# MusselGapeTracker_RevE.net
KiCad netlist of a schematic drawn in EAGLE
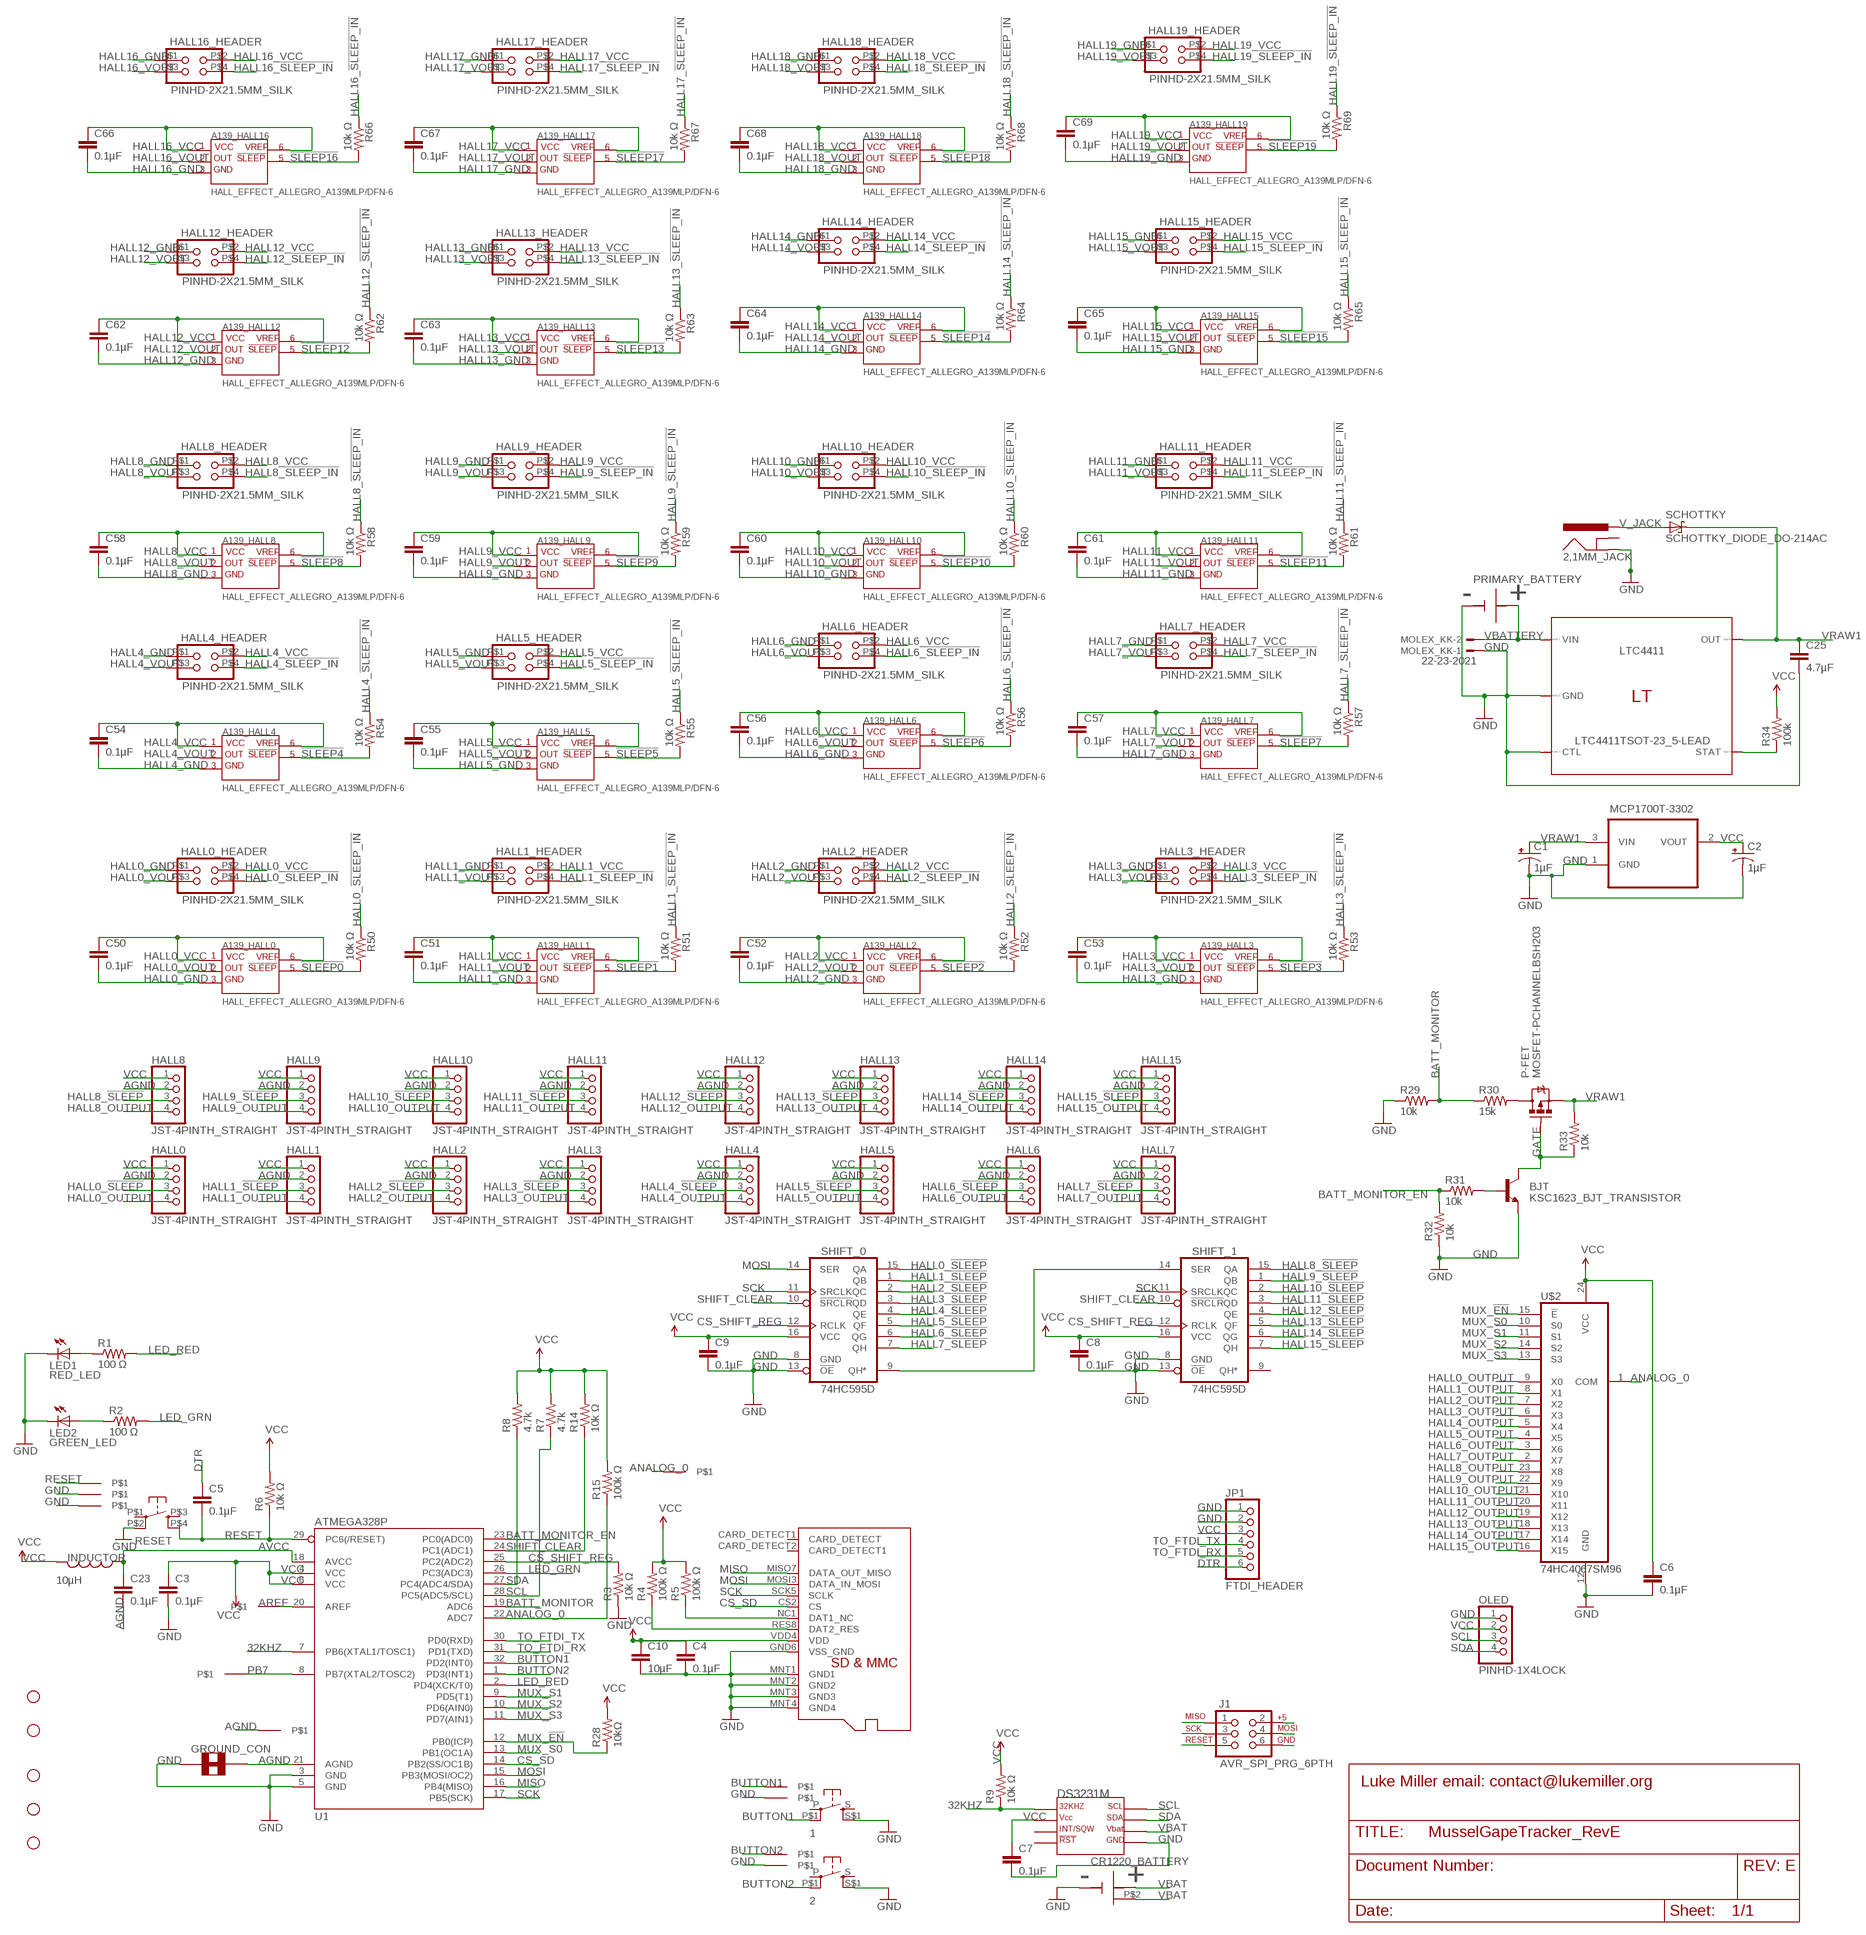
[diagram p0: schematic, sheet 1]

(export (version "E")
  (design (tool "Eeschema 10.0.6"))
  (components
    (comp (ref "1")
      (value "PUSHBUTTON_DPST_SMDSTANDARD")
      (footprint "eagle-import:PUSHBUTTON_DPST_SMD")
      (libsource (lib "eagle-import") (part "PUSHBUTTON_DPST_SMDSTANDARD"))
    )
    (comp (ref "2")
      (value "PUSHBUTTON_DPST_SMDSTANDARD")
      (footprint "eagle-import:PUSHBUTTON_DPST_SMD")
      (libsource (lib "eagle-import") (part "PUSHBUTTON_DPST_SMDSTANDARD"))
    )
    (comp (ref "2,1MM_JACK")
      (value "POWER_JACK_2,1MM")
      (footprint "eagle-import:POWER_JACK_DC_2,1MM")
      (libsource (lib "eagle-import") (part "POWER_JACK_2,1MM"))
    )
    (comp (ref "A139_HALL0")
      (value "HALL_EFFECT_ALLEGRO_A139MLP/DFN-6")
      (footprint "eagle-import:A139__HALL_EFFECT")
      (libsource (lib "eagle-import") (part "HALL_EFFECT_ALLEGRO_A139MLP/DFN-6"))
    )
    (comp (ref "A139_HALL1")
      (value "HALL_EFFECT_ALLEGRO_A139MLP/DFN-6")
      (footprint "eagle-import:A139__HALL_EFFECT")
      (libsource (lib "eagle-import") (part "HALL_EFFECT_ALLEGRO_A139MLP/DFN-6"))
    )
    (comp (ref "A139_HALL2")
      (value "HALL_EFFECT_ALLEGRO_A139MLP/DFN-6")
      (footprint "eagle-import:A139__HALL_EFFECT")
      (libsource (lib "eagle-import") (part "HALL_EFFECT_ALLEGRO_A139MLP/DFN-6"))
    )
    (comp (ref "A139_HALL3")
      (value "HALL_EFFECT_ALLEGRO_A139MLP/DFN-6")
      (footprint "eagle-import:A139__HALL_EFFECT")
      (libsource (lib "eagle-import") (part "HALL_EFFECT_ALLEGRO_A139MLP/DFN-6"))
    )
    (comp (ref "A139_HALL4")
      (value "HALL_EFFECT_ALLEGRO_A139MLP/DFN-6")
      (footprint "eagle-import:A139__HALL_EFFECT")
      (libsource (lib "eagle-import") (part "HALL_EFFECT_ALLEGRO_A139MLP/DFN-6"))
    )
    (comp (ref "A139_HALL5")
      (value "HALL_EFFECT_ALLEGRO_A139MLP/DFN-6")
      (footprint "eagle-import:A139__HALL_EFFECT")
      (libsource (lib "eagle-import") (part "HALL_EFFECT_ALLEGRO_A139MLP/DFN-6"))
    )
    (comp (ref "A139_HALL6")
      (value "HALL_EFFECT_ALLEGRO_A139MLP/DFN-6")
      (footprint "eagle-import:A139__HALL_EFFECT")
      (libsource (lib "eagle-import") (part "HALL_EFFECT_ALLEGRO_A139MLP/DFN-6"))
    )
    (comp (ref "A139_HALL7")
      (value "HALL_EFFECT_ALLEGRO_A139MLP/DFN-6")
      (footprint "eagle-import:A139__HALL_EFFECT")
      (libsource (lib "eagle-import") (part "HALL_EFFECT_ALLEGRO_A139MLP/DFN-6"))
    )
    (comp (ref "A139_HALL8")
      (value "HALL_EFFECT_ALLEGRO_A139MLP/DFN-6")
      (footprint "eagle-import:A139__HALL_EFFECT")
      (libsource (lib "eagle-import") (part "HALL_EFFECT_ALLEGRO_A139MLP/DFN-6"))
    )
    (comp (ref "A139_HALL9")
      (value "HALL_EFFECT_ALLEGRO_A139MLP/DFN-6")
      (footprint "eagle-import:A139__HALL_EFFECT")
      (libsource (lib "eagle-import") (part "HALL_EFFECT_ALLEGRO_A139MLP/DFN-6"))
    )
    (comp (ref "A139_HALL10")
      (value "HALL_EFFECT_ALLEGRO_A139MLP/DFN-6")
      (footprint "eagle-import:A139__HALL_EFFECT")
      (libsource (lib "eagle-import") (part "HALL_EFFECT_ALLEGRO_A139MLP/DFN-6"))
    )
    (comp (ref "A139_HALL11")
      (value "HALL_EFFECT_ALLEGRO_A139MLP/DFN-6")
      (footprint "eagle-import:A139__HALL_EFFECT")
      (libsource (lib "eagle-import") (part "HALL_EFFECT_ALLEGRO_A139MLP/DFN-6"))
    )
    (comp (ref "A139_HALL12")
      (value "HALL_EFFECT_ALLEGRO_A139MLP/DFN-6")
      (footprint "eagle-import:A139__HALL_EFFECT")
      (libsource (lib "eagle-import") (part "HALL_EFFECT_ALLEGRO_A139MLP/DFN-6"))
    )
    (comp (ref "A139_HALL13")
      (value "HALL_EFFECT_ALLEGRO_A139MLP/DFN-6")
      (footprint "eagle-import:A139__HALL_EFFECT")
      (libsource (lib "eagle-import") (part "HALL_EFFECT_ALLEGRO_A139MLP/DFN-6"))
    )
    (comp (ref "A139_HALL14")
      (value "HALL_EFFECT_ALLEGRO_A139MLP/DFN-6")
      (footprint "eagle-import:A139__HALL_EFFECT")
      (libsource (lib "eagle-import") (part "HALL_EFFECT_ALLEGRO_A139MLP/DFN-6"))
    )
    (comp (ref "A139_HALL15")
      (value "HALL_EFFECT_ALLEGRO_A139MLP/DFN-6")
      (footprint "eagle-import:A139__HALL_EFFECT")
      (libsource (lib "eagle-import") (part "HALL_EFFECT_ALLEGRO_A139MLP/DFN-6"))
    )
    (comp (ref "A139_HALL16")
      (value "HALL_EFFECT_ALLEGRO_A139MLP/DFN-6")
      (footprint "eagle-import:A139__HALL_EFFECT")
      (libsource (lib "eagle-import") (part "HALL_EFFECT_ALLEGRO_A139MLP/DFN-6"))
    )
    (comp (ref "A139_HALL17")
      (value "HALL_EFFECT_ALLEGRO_A139MLP/DFN-6")
      (footprint "eagle-import:A139__HALL_EFFECT")
      (libsource (lib "eagle-import") (part "HALL_EFFECT_ALLEGRO_A139MLP/DFN-6"))
    )
    (comp (ref "A139_HALL18")
      (value "HALL_EFFECT_ALLEGRO_A139MLP/DFN-6")
      (footprint "eagle-import:A139__HALL_EFFECT")
      (libsource (lib "eagle-import") (part "HALL_EFFECT_ALLEGRO_A139MLP/DFN-6"))
    )
    (comp (ref "A139_HALL19")
      (value "HALL_EFFECT_ALLEGRO_A139MLP/DFN-6")
      (footprint "eagle-import:A139__HALL_EFFECT")
      (libsource (lib "eagle-import") (part "HALL_EFFECT_ALLEGRO_A139MLP/DFN-6"))
    )
    (comp (ref "BJT")
      (value "KSC1623_BJT_TRANSISTOR")
      (footprint "eagle-import:SOT23")
      (libsource (lib "eagle-import") (part "KSC1623_BJT_TRANSISTOR"))
    )
    (comp (ref "C1")
      (value "1µF")
      (footprint "eagle-import:PANASONIC_B")
      (libsource (lib "eagle-import") (part "CPOL-USB"))
    )
    (comp (ref "C2")
      (value "1µF")
      (footprint "eagle-import:PANASONIC_B")
      (libsource (lib "eagle-import") (part "CPOL-USB"))
    )
    (comp (ref "C3")
      (value "0.1µF")
      (footprint "eagle-import:0603")
      (libsource (lib "eagle-import") (part "CAP0603"))
    )
    (comp (ref "C4")
      (value "0.1µF")
      (footprint "eagle-import:0603")
      (libsource (lib "eagle-import") (part "CAP0603"))
    )
    (comp (ref "C5")
      (value "0.1µF")
      (footprint "eagle-import:0603")
      (libsource (lib "eagle-import") (part "CAP0603"))
    )
    (comp (ref "C6")
      (value "0.1µF")
      (footprint "eagle-import:0603")
      (libsource (lib "eagle-import") (part "CAP0603"))
    )
    (comp (ref "C7")
      (value "0.1µF")
      (footprint "eagle-import:0603")
      (libsource (lib "eagle-import") (part "CAP0603"))
    )
    (comp (ref "C8")
      (value "0.1µF")
      (footprint "eagle-import:0603")
      (libsource (lib "eagle-import") (part "CAP0603"))
    )
    (comp (ref "C9")
      (value "0.1µF")
      (footprint "eagle-import:0603")
      (libsource (lib "eagle-import") (part "CAP0603"))
    )
    (comp (ref "C10")
      (value "10µF")
      (footprint "eagle-import:0603")
      (libsource (lib "eagle-import") (part "CAP0603"))
    )
    (comp (ref "C23")
      (value "0.1µF")
      (footprint "eagle-import:0603")
      (libsource (lib "eagle-import") (part "CAP0603"))
    )
    (comp (ref "C25")
      (value "4.7µF")
      (footprint "eagle-import:0603")
      (libsource (lib "eagle-import") (part "CAP0603"))
    )
    (comp (ref "C50")
      (value "0.1µF")
      (footprint "eagle-import:0603")
      (libsource (lib "eagle-import") (part "CAP0603"))
    )
    (comp (ref "C51")
      (value "0.1µF")
      (footprint "eagle-import:0603")
      (libsource (lib "eagle-import") (part "CAP0603"))
    )
    (comp (ref "C52")
      (value "0.1µF")
      (footprint "eagle-import:0603")
      (libsource (lib "eagle-import") (part "CAP0603"))
    )
    (comp (ref "C53")
      (value "0.1µF")
      (footprint "eagle-import:0603")
      (libsource (lib "eagle-import") (part "CAP0603"))
    )
    (comp (ref "C54")
      (value "0.1µF")
      (footprint "eagle-import:0603")
      (libsource (lib "eagle-import") (part "CAP0603"))
    )
    (comp (ref "C55")
      (value "0.1µF")
      (footprint "eagle-import:0603")
      (libsource (lib "eagle-import") (part "CAP0603"))
    )
    (comp (ref "C56")
      (value "0.1µF")
      (footprint "eagle-import:0603")
      (libsource (lib "eagle-import") (part "CAP0603"))
    )
    (comp (ref "C57")
      (value "0.1µF")
      (footprint "eagle-import:0603")
      (libsource (lib "eagle-import") (part "CAP0603"))
    )
    (comp (ref "C58")
      (value "0.1µF")
      (footprint "eagle-import:0603")
      (libsource (lib "eagle-import") (part "CAP0603"))
    )
    (comp (ref "C59")
      (value "0.1µF")
      (footprint "eagle-import:0603")
      (libsource (lib "eagle-import") (part "CAP0603"))
    )
    (comp (ref "C60")
      (value "0.1µF")
      (footprint "eagle-import:0603")
      (libsource (lib "eagle-import") (part "CAP0603"))
    )
    (comp (ref "C61")
      (value "0.1µF")
      (footprint "eagle-import:0603")
      (libsource (lib "eagle-import") (part "CAP0603"))
    )
    (comp (ref "C62")
      (value "0.1µF")
      (footprint "eagle-import:0603")
      (libsource (lib "eagle-import") (part "CAP0603"))
    )
    (comp (ref "C63")
      (value "0.1µF")
      (footprint "eagle-import:0603")
      (libsource (lib "eagle-import") (part "CAP0603"))
    )
    (comp (ref "C64")
      (value "0.1µF")
      (footprint "eagle-import:0603")
      (libsource (lib "eagle-import") (part "CAP0603"))
    )
    (comp (ref "C65")
      (value "0.1µF")
      (footprint "eagle-import:0603")
      (libsource (lib "eagle-import") (part "CAP0603"))
    )
    (comp (ref "C66")
      (value "0.1µF")
      (footprint "eagle-import:0603")
      (libsource (lib "eagle-import") (part "CAP0603"))
    )
    (comp (ref "C67")
      (value "0.1µF")
      (footprint "eagle-import:0603")
      (libsource (lib "eagle-import") (part "CAP0603"))
    )
    (comp (ref "C68")
      (value "0.1µF")
      (footprint "eagle-import:0603")
      (libsource (lib "eagle-import") (part "CAP0603"))
    )
    (comp (ref "C69")
      (value "0.1µF")
      (footprint "eagle-import:0603")
      (libsource (lib "eagle-import") (part "CAP0603"))
    )
    (comp (ref "CR1220_BATTERY")
      (value "CR1220_BATTERY_HOLDERSMD")
      (footprint "eagle-import:CR1220_BATTERY_HOLDER_SMD")
      (libsource (lib "eagle-import") (part "CR1220_BATTERY_HOLDERSMD"))
    )
    (comp (ref "DS3231M")
      (value "DS3231MSOIC-8")
      (footprint "eagle-import:DS3231M_SOIC8")
      (libsource (lib "eagle-import") (part "DS3231MSOIC-8"))
    )
    (comp (ref "GND")
      (value "PINHD-1X1SMALL")
      (footprint "eagle-import:1X01_SMALL")
      (libsource (lib "eagle-import") (part "PINHD-1X1SMALL"))
    )
    (comp (ref "GROUND_CON")
      (value "SOLDER_JUMPER_TRACESTANDARD")
      (footprint "eagle-import:SJ_2S-TRACE")
      (libsource (lib "eagle-import") (part "SOLDER_JUMPER_TRACESTANDARD"))
    )
    (comp (ref "HALL0")
      (value "JST-4PINTH_STRAIGHT")
      (footprint "eagle-import:JST-PH-4-THM")
      (libsource (lib "eagle-import") (part "JST-4PINTH_STRAIGHT"))
    )
    (comp (ref "HALL0_HEADER")
      (value "PINHD-2X21.5MM_SILK")
      (footprint "eagle-import:2X2_1.5MM")
      (libsource (lib "eagle-import") (part "PINHD-2X21.5MM_SILK"))
    )
    (comp (ref "HALL1")
      (value "JST-4PINTH_STRAIGHT")
      (footprint "eagle-import:JST-PH-4-THM")
      (libsource (lib "eagle-import") (part "JST-4PINTH_STRAIGHT"))
    )
    (comp (ref "HALL1_HEADER")
      (value "PINHD-2X21.5MM_SILK")
      (footprint "eagle-import:2X2_1.5MM")
      (libsource (lib "eagle-import") (part "PINHD-2X21.5MM_SILK"))
    )
    (comp (ref "HALL2")
      (value "JST-4PINTH_STRAIGHT")
      (footprint "eagle-import:JST-PH-4-THM")
      (libsource (lib "eagle-import") (part "JST-4PINTH_STRAIGHT"))
    )
    (comp (ref "HALL2_HEADER")
      (value "PINHD-2X21.5MM_SILK")
      (footprint "eagle-import:2X2_1.5MM")
      (libsource (lib "eagle-import") (part "PINHD-2X21.5MM_SILK"))
    )
    (comp (ref "HALL3")
      (value "JST-4PINTH_STRAIGHT")
      (footprint "eagle-import:JST-PH-4-THM")
      (libsource (lib "eagle-import") (part "JST-4PINTH_STRAIGHT"))
    )
    (comp (ref "HALL3_HEADER")
      (value "PINHD-2X21.5MM_SILK")
      (footprint "eagle-import:2X2_1.5MM")
      (libsource (lib "eagle-import") (part "PINHD-2X21.5MM_SILK"))
    )
    (comp (ref "HALL4")
      (value "JST-4PINTH_STRAIGHT")
      (footprint "eagle-import:JST-PH-4-THM")
      (libsource (lib "eagle-import") (part "JST-4PINTH_STRAIGHT"))
    )
    (comp (ref "HALL4_HEADER")
      (value "PINHD-2X21.5MM_SILK")
      (footprint "eagle-import:2X2_1.5MM")
      (libsource (lib "eagle-import") (part "PINHD-2X21.5MM_SILK"))
    )
    (comp (ref "HALL5")
      (value "JST-4PINTH_STRAIGHT")
      (footprint "eagle-import:JST-PH-4-THM")
      (libsource (lib "eagle-import") (part "JST-4PINTH_STRAIGHT"))
    )
    (comp (ref "HALL5_HEADER")
      (value "PINHD-2X21.5MM_SILK")
      (footprint "eagle-import:2X2_1.5MM")
      (libsource (lib "eagle-import") (part "PINHD-2X21.5MM_SILK"))
    )
    (comp (ref "HALL6")
      (value "JST-4PINTH_STRAIGHT")
      (footprint "eagle-import:JST-PH-4-THM")
      (libsource (lib "eagle-import") (part "JST-4PINTH_STRAIGHT"))
    )
    (comp (ref "HALL6_HEADER")
      (value "PINHD-2X21.5MM_SILK")
      (footprint "eagle-import:2X2_1.5MM")
      (libsource (lib "eagle-import") (part "PINHD-2X21.5MM_SILK"))
    )
    (comp (ref "HALL7")
      (value "JST-4PINTH_STRAIGHT")
      (footprint "eagle-import:JST-PH-4-THM")
      (libsource (lib "eagle-import") (part "JST-4PINTH_STRAIGHT"))
    )
    (comp (ref "HALL7_HEADER")
      (value "PINHD-2X21.5MM_SILK")
      (footprint "eagle-import:2X2_1.5MM")
      (libsource (lib "eagle-import") (part "PINHD-2X21.5MM_SILK"))
    )
    (comp (ref "HALL8")
      (value "JST-4PINTH_STRAIGHT")
      (footprint "eagle-import:JST-PH-4-THM")
      (libsource (lib "eagle-import") (part "JST-4PINTH_STRAIGHT"))
    )
    (comp (ref "HALL8_HEADER")
      (value "PINHD-2X21.5MM_SILK")
      (footprint "eagle-import:2X2_1.5MM")
      (libsource (lib "eagle-import") (part "PINHD-2X21.5MM_SILK"))
    )
    (comp (ref "HALL9")
      (value "JST-4PINTH_STRAIGHT")
      (footprint "eagle-import:JST-PH-4-THM")
      (libsource (lib "eagle-import") (part "JST-4PINTH_STRAIGHT"))
    )
    (comp (ref "HALL9_HEADER")
      (value "PINHD-2X21.5MM_SILK")
      (footprint "eagle-import:2X2_1.5MM")
      (libsource (lib "eagle-import") (part "PINHD-2X21.5MM_SILK"))
    )
    (comp (ref "HALL10")
      (value "JST-4PINTH_STRAIGHT")
      (footprint "eagle-import:JST-PH-4-THM")
      (libsource (lib "eagle-import") (part "JST-4PINTH_STRAIGHT"))
    )
    (comp (ref "HALL10_HEADER")
      (value "PINHD-2X21.5MM_SILK")
      (footprint "eagle-import:2X2_1.5MM")
      (libsource (lib "eagle-import") (part "PINHD-2X21.5MM_SILK"))
    )
    (comp (ref "HALL11")
      (value "JST-4PINTH_STRAIGHT")
      (footprint "eagle-import:JST-PH-4-THM")
      (libsource (lib "eagle-import") (part "JST-4PINTH_STRAIGHT"))
    )
    (comp (ref "HALL11_HEADER")
      (value "PINHD-2X21.5MM_SILK")
      (footprint "eagle-import:2X2_1.5MM")
      (libsource (lib "eagle-import") (part "PINHD-2X21.5MM_SILK"))
    )
    (comp (ref "HALL12")
      (value "JST-4PINTH_STRAIGHT")
      (footprint "eagle-import:JST-PH-4-THM")
      (libsource (lib "eagle-import") (part "JST-4PINTH_STRAIGHT"))
    )
    (comp (ref "HALL12_HEADER")
      (value "PINHD-2X21.5MM_SILK")
      (footprint "eagle-import:2X2_1.5MM")
      (libsource (lib "eagle-import") (part "PINHD-2X21.5MM_SILK"))
    )
    (comp (ref "HALL13")
      (value "JST-4PINTH_STRAIGHT")
      (footprint "eagle-import:JST-PH-4-THM")
      (libsource (lib "eagle-import") (part "JST-4PINTH_STRAIGHT"))
    )
    (comp (ref "HALL13_HEADER")
      (value "PINHD-2X21.5MM_SILK")
      (footprint "eagle-import:2X2_1.5MM")
      (libsource (lib "eagle-import") (part "PINHD-2X21.5MM_SILK"))
    )
    (comp (ref "HALL14")
      (value "JST-4PINTH_STRAIGHT")
      (footprint "eagle-import:JST-PH-4-THM")
      (libsource (lib "eagle-import") (part "JST-4PINTH_STRAIGHT"))
    )
    (comp (ref "HALL14_HEADER")
      (value "PINHD-2X21.5MM_SILK")
      (footprint "eagle-import:2X2_1.5MM")
      (libsource (lib "eagle-import") (part "PINHD-2X21.5MM_SILK"))
    )
    (comp (ref "HALL15")
      (value "JST-4PINTH_STRAIGHT")
      (footprint "eagle-import:JST-PH-4-THM")
      (libsource (lib "eagle-import") (part "JST-4PINTH_STRAIGHT"))
    )
    (comp (ref "HALL15_HEADER")
      (value "PINHD-2X21.5MM_SILK")
      (footprint "eagle-import:2X2_1.5MM")
      (libsource (lib "eagle-import") (part "PINHD-2X21.5MM_SILK"))
    )
    (comp (ref "HALL16_HEADER")
      (value "PINHD-2X21.5MM_SILK")
      (footprint "eagle-import:2X2_1.5MM")
      (libsource (lib "eagle-import") (part "PINHD-2X21.5MM_SILK"))
    )
    (comp (ref "HALL17_HEADER")
      (value "PINHD-2X21.5MM_SILK")
      (footprint "eagle-import:2X2_1.5MM")
      (libsource (lib "eagle-import") (part "PINHD-2X21.5MM_SILK"))
    )
    (comp (ref "HALL18_HEADER")
      (value "PINHD-2X21.5MM_SILK")
      (footprint "eagle-import:2X2_1.5MM")
      (libsource (lib "eagle-import") (part "PINHD-2X21.5MM_SILK"))
    )
    (comp (ref "HALL19_HEADER")
      (value "PINHD-2X21.5MM_SILK")
      (footprint "eagle-import:2X2_1.5MM")
      (libsource (lib "eagle-import") (part "PINHD-2X21.5MM_SILK"))
    )
    (comp (ref "INDUCTOR")
      (value "10µH")
      (footprint "eagle-import:I_0805")
      (libsource (lib "eagle-import") (part "INDUCTOR0805_TY"))
    )
    (comp (ref "J1")
      (value "AVR_SPI_PRG_6PTH")
      (footprint "eagle-import:2X3")
      (libsource (lib "eagle-import") (part "AVR_SPI_PRG_6PTH"))
    )
    (comp (ref "JP1")
      (value "FTDI_HEADER")
      (footprint "eagle-import:1X06-RIGHT_ANGLE")
      (libsource (lib "eagle-import") (part "PINHD-1X6RA"))
    )
    (comp (ref "LED1")
      (value "RED_LED")
      (footprint "eagle-import:CHIPLED_0805")
      (libsource (lib "eagle-import") (part "LED0805"))
    )
    (comp (ref "LED2")
      (value "GREEN_LED")
      (footprint "eagle-import:CHIPLED_0805")
      (libsource (lib "eagle-import") (part "LED0805"))
    )
    (comp (ref "LTC4411")
      (value "LTC4411TSOT-23_5-LEAD")
      (footprint "eagle-import:TSOT-23_5-LEAD")
      (libsource (lib "eagle-import") (part "LTC4411TSOT-23_5-LEAD"))
    )
    (comp (ref "MCP1700T-3302")
      (value "MCP1700T-3302E/TT")
      (footprint "eagle-import:SOT95P237X112-3N")
      (libsource (lib "eagle-import") (part "MCP1700T-3302E/TT"))
    )
    (comp (ref "MOLEX_KK")
      (value "22-23-2021")
      (footprint "eagle-import:22-23-2021")
      (fields (field (name "MF") "MOLEX"))
      (libsource (lib "eagle-import") (part "22-23-2021"))
    )
    (comp (ref "OLED")
      (value "PINHD-1X4LOCK")
      (footprint "eagle-import:1X04_LOCK")
      (libsource (lib "eagle-import") (part "PINHD-1X4LOCK"))
    )
    (comp (ref "P-FET")
      (value "MOSFET-PCHANNELBSH203")
      (footprint "eagle-import:SOT23-3")
      (libsource (lib "eagle-import") (part "MOSFET-PCHANNELBSH203"))
    )
    (comp (ref "PB7")
      (value "PINHD-1X1SMALL")
      (footprint "eagle-import:1X01_SMALL")
      (libsource (lib "eagle-import") (part "PINHD-1X1SMALL"))
    )
    (comp (ref "PRIMARY_BATTERY")
      (value "BATTERY_4XAA")
      (footprint "eagle-import:BATTERY_4XAA_PTH")
      (libsource (lib "eagle-import") (part "BATTERY_4XAA"))
    )
    (comp (ref "R1")
      (value "100 Ω")
      (footprint "eagle-import:R0603")
      (libsource (lib "eagle-import") (part "RESISTOR_SMDR0603"))
    )
    (comp (ref "R2")
      (value "100 Ω")
      (footprint "eagle-import:R0603")
      (libsource (lib "eagle-import") (part "RESISTOR_SMDR0603"))
    )
    (comp (ref "R3")
      (value "10k Ω")
      (footprint "eagle-import:R0603")
      (libsource (lib "eagle-import") (part "RESISTOR_SMDR0603"))
    )
    (comp (ref "R4")
      (value "100k Ω")
      (footprint "eagle-import:R0603")
      (libsource (lib "eagle-import") (part "RESISTOR_SMDR0603"))
    )
    (comp (ref "R5")
      (value "100k Ω")
      (footprint "eagle-import:R0603")
      (libsource (lib "eagle-import") (part "RESISTOR_SMDR0603"))
    )
    (comp (ref "R6")
      (value "10k Ω")
      (footprint "eagle-import:R0603")
      (libsource (lib "eagle-import") (part "RESISTOR_SMDR0603"))
    )
    (comp (ref "R7")
      (value "4.7k")
      (footprint "eagle-import:R0603")
      (libsource (lib "eagle-import") (part "RESISTOR_SMDR0603"))
    )
    (comp (ref "R8")
      (value "4.7k")
      (footprint "eagle-import:R0603")
      (libsource (lib "eagle-import") (part "RESISTOR_SMDR0603"))
    )
    (comp (ref "R9")
      (value "10k Ω")
      (footprint "eagle-import:R0603")
      (libsource (lib "eagle-import") (part "RESISTOR_SMDR0603"))
    )
    (comp (ref "R14")
      (value "10k Ω")
      (footprint "eagle-import:R0603")
      (libsource (lib "eagle-import") (part "RESISTOR_SMDR0603"))
    )
    (comp (ref "R15")
      (value "100k Ω")
      (footprint "eagle-import:R0603")
      (libsource (lib "eagle-import") (part "RESISTOR_SMDR0603"))
    )
    (comp (ref "R28")
      (value "10kΩ")
      (footprint "eagle-import:R0603")
      (libsource (lib "eagle-import") (part "RESISTOR_SMDR0603"))
    )
    (comp (ref "R29")
      (value "10k")
      (footprint "eagle-import:R0603")
      (libsource (lib "eagle-import") (part "RESISTOR_SMDR0603"))
    )
    (comp (ref "R30")
      (value "15k")
      (footprint "eagle-import:R0603")
      (libsource (lib "eagle-import") (part "RESISTOR_SMDR0603"))
    )
    (comp (ref "R31")
      (value "10k")
      (footprint "eagle-import:R0603")
      (libsource (lib "eagle-import") (part "RESISTOR_SMDR0603"))
    )
    (comp (ref "R32")
      (value "10k")
      (footprint "eagle-import:R0603")
      (libsource (lib "eagle-import") (part "RESISTOR_SMDR0603"))
    )
    (comp (ref "R33")
      (value "10k")
      (footprint "eagle-import:R0603")
      (libsource (lib "eagle-import") (part "RESISTOR_SMDR0603"))
    )
    (comp (ref "R34")
      (value "100k")
      (footprint "eagle-import:R0603")
      (libsource (lib "eagle-import") (part "RESISTOR_SMDR0603"))
    )
    (comp (ref "R50")
      (value "10k Ω")
      (footprint "eagle-import:R0603")
      (libsource (lib "eagle-import") (part "RESISTOR_SMDR0603"))
    )
    (comp (ref "R51")
      (value "10k Ω")
      (footprint "eagle-import:R0603")
      (libsource (lib "eagle-import") (part "RESISTOR_SMDR0603"))
    )
    (comp (ref "R52")
      (value "10k Ω")
      (footprint "eagle-import:R0603")
      (libsource (lib "eagle-import") (part "RESISTOR_SMDR0603"))
    )
    (comp (ref "R53")
      (value "10k Ω")
      (footprint "eagle-import:R0603")
      (libsource (lib "eagle-import") (part "RESISTOR_SMDR0603"))
    )
    (comp (ref "R54")
      (value "10k Ω")
      (footprint "eagle-import:R0603")
      (libsource (lib "eagle-import") (part "RESISTOR_SMDR0603"))
    )
    (comp (ref "R55")
      (value "10k Ω")
      (footprint "eagle-import:R0603")
      (libsource (lib "eagle-import") (part "RESISTOR_SMDR0603"))
    )
    (comp (ref "R56")
      (value "10k Ω")
      (footprint "eagle-import:R0603")
      (libsource (lib "eagle-import") (part "RESISTOR_SMDR0603"))
    )
    (comp (ref "R57")
      (value "10k Ω")
      (footprint "eagle-import:R0603")
      (libsource (lib "eagle-import") (part "RESISTOR_SMDR0603"))
    )
    (comp (ref "R58")
      (value "10k Ω")
      (footprint "eagle-import:R0603")
      (libsource (lib "eagle-import") (part "RESISTOR_SMDR0603"))
    )
    (comp (ref "R59")
      (value "10k Ω")
      (footprint "eagle-import:R0603")
      (libsource (lib "eagle-import") (part "RESISTOR_SMDR0603"))
    )
    (comp (ref "R60")
      (value "10k Ω")
      (footprint "eagle-import:R0603")
      (libsource (lib "eagle-import") (part "RESISTOR_SMDR0603"))
    )
    (comp (ref "R61")
      (value "10k Ω")
      (footprint "eagle-import:R0603")
      (libsource (lib "eagle-import") (part "RESISTOR_SMDR0603"))
    )
    (comp (ref "R62")
      (value "10k Ω")
      (footprint "eagle-import:R0603")
      (libsource (lib "eagle-import") (part "RESISTOR_SMDR0603"))
    )
    (comp (ref "R63")
      (value "10k Ω")
      (footprint "eagle-import:R0603")
      (libsource (lib "eagle-import") (part "RESISTOR_SMDR0603"))
    )
    (comp (ref "R64")
      (value "10k Ω")
      (footprint "eagle-import:R0603")
      (libsource (lib "eagle-import") (part "RESISTOR_SMDR0603"))
    )
    (comp (ref "R65")
      (value "10k Ω")
      (footprint "eagle-import:R0603")
      (libsource (lib "eagle-import") (part "RESISTOR_SMDR0603"))
    )
    (comp (ref "R66")
      (value "10k Ω")
      (footprint "eagle-import:R0603")
      (libsource (lib "eagle-import") (part "RESISTOR_SMDR0603"))
    )
    (comp (ref "R67")
      (value "10k Ω")
      (footprint "eagle-import:R0603")
      (libsource (lib "eagle-import") (part "RESISTOR_SMDR0603"))
    )
    (comp (ref "R68")
      (value "10k Ω")
      (footprint "eagle-import:R0603")
      (libsource (lib "eagle-import") (part "RESISTOR_SMDR0603"))
    )
    (comp (ref "R69")
      (value "10k Ω")
      (footprint "eagle-import:R0603")
      (libsource (lib "eagle-import") (part "RESISTOR_SMDR0603"))
    )
    (comp (ref "RESET")
      (value "PUSHBUTTON_DPST_SMDSMALL")
      (footprint "eagle-import:PUSHBUTTON_SPST_PTS525_SERIES")
      (libsource (lib "eagle-import") (part "PUSHBUTTON_DPST_SMDSMALL"))
    )
    (comp (ref "SCHOTTKY")
      (value "SCHOTTKY_DIODE_DO-214AC")
      (footprint "eagle-import:DO214AC")
      (libsource (lib "eagle-import") (part "SCHOTTKY_DIODE_DO-214AC"))
    )
    (comp (ref "SHIFT_0")
      (value "74HC595D")
      (footprint "eagle-import:SO16")
      (libsource (lib "eagle-import") (part "74HC595D"))
    )
    (comp (ref "SHIFT_1")
      (value "74HC595D")
      (footprint "eagle-import:SO16")
      (libsource (lib "eagle-import") (part "74HC595D"))
    )
    (comp (ref "STANDOFF1")
      (value "STAND-OFF4-40")
      (footprint "eagle-import:STAND-OFF")
      (libsource (lib "eagle-import") (part "STAND-OFF4-40"))
    )
    (comp (ref "STANDOFF2")
      (value "STAND-OFF4-40")
      (footprint "eagle-import:STAND-OFF")
      (libsource (lib "eagle-import") (part "STAND-OFF4-40"))
    )
    (comp (ref "STANDOFF3")
      (value "STAND-OFF4-40")
      (footprint "eagle-import:STAND-OFF")
      (libsource (lib "eagle-import") (part "STAND-OFF4-40"))
    )
    (comp (ref "STANDOFF4_M2")
      (value "STAND-OFFM2")
      (footprint "eagle-import:STAND-OFF_M2")
      (libsource (lib "eagle-import") (part "STAND-OFFM2"))
    )
    (comp (ref "STANDOFF5_M2")
      (value "STAND-OFFM2")
      (footprint "eagle-import:STAND-OFF_M2")
      (libsource (lib "eagle-import") (part "STAND-OFFM2"))
    )
    (comp (ref "U$1")
      (value "MICROSD_MOLEX_REVERSECURRENT")
      (footprint "eagle-import:MICROSD_SOCKET_MOLEX_REVERSEMOUNT")
      (libsource (lib "eagle-import") (part "MICROSD_MOLEX_REVERSECURRENT"))
    )
    (comp (ref "U$2")
      (value "74HC4067SM96")
      (footprint "eagle-import:SSOP24")
      (libsource (lib "eagle-import") (part "74HC4067SM96"))
    )
    (comp (ref "U$3")
      (value "PINHD-1X1SMALL")
      (footprint "eagle-import:1X01_SMALL")
      (libsource (lib "eagle-import") (part "PINHD-1X1SMALL"))
    )
    (comp (ref "U$4")
      (value "PINHD-1X1SMALL")
      (footprint "eagle-import:1X01_SMALL")
      (libsource (lib "eagle-import") (part "PINHD-1X1SMALL"))
    )
    (comp (ref "U$6")
      (value "PINHD-1X1SMALL")
      (footprint "eagle-import:1X01_SMALL")
      (libsource (lib "eagle-import") (part "PINHD-1X1SMALL"))
    )
    (comp (ref "U$7")
      (value "PINHD-1X1SMALL")
      (footprint "eagle-import:1X01_SMALL")
      (libsource (lib "eagle-import") (part "PINHD-1X1SMALL"))
    )
    (comp (ref "U$8")
      (value "PINHD-1X1SMALL")
      (footprint "eagle-import:1X01_SMALL")
      (libsource (lib "eagle-import") (part "PINHD-1X1SMALL"))
    )
    (comp (ref "U$9")
      (value "PINHD-1X1SMALL")
      (footprint "eagle-import:1X01_SMALL")
      (libsource (lib "eagle-import") (part "PINHD-1X1SMALL"))
    )
    (comp (ref "U$10")
      (value "PINHD-1X1SMALL")
      (footprint "eagle-import:1X01_SMALL")
      (libsource (lib "eagle-import") (part "PINHD-1X1SMALL"))
    )
    (comp (ref "U$11")
      (value "PINHD-1X1SMALL")
      (footprint "eagle-import:1X01_SMALL")
      (libsource (lib "eagle-import") (part "PINHD-1X1SMALL"))
    )
    (comp (ref "U$17")
      (value "PINHD-1X1SMALL")
      (footprint "eagle-import:1X01_SMALL")
      (libsource (lib "eagle-import") (part "PINHD-1X1SMALL"))
    )
    (comp (ref "U1")
      (value "ATMEGA328P")
      (footprint "eagle-import:TQFP32-08")
      (libsource (lib "eagle-import") (part "ATMEGA328_SMT"))
    )
  )
  (nets
    (net (code "1") (name "/32KHZ") (class "Default")
      (node (ref "DS3231M") (pin "1") (pinfunction "P$1_32KHZ_1") (pintype "bidirectional"))
      (node (ref "R9") (pin "1") (pinfunction "1_1") (pintype "passive"))
      (node (ref "U1") (pin "7") (pinfunction "PB6(XTAL1/TOSC1)_7") (pintype "bidirectional"))
    )
    (net (code "2") (name "/AGND") (class "Default")
      (node (ref "C23") (pin "2") (pinfunction "2_2") (pintype "passive"))
      (node (ref "GROUND_CON") (pin "2") (pinfunction "P$2_2") (pintype "bidirectional"))
      (node (ref "HALL0") (pin "2") (pinfunction "2_2") (pintype "passive"))
      (node (ref "HALL1") (pin "2") (pinfunction "2_2") (pintype "passive"))
      (node (ref "HALL10") (pin "2") (pinfunction "2_2") (pintype "passive"))
      (node (ref "HALL11") (pin "2") (pinfunction "2_2") (pintype "passive"))
      (node (ref "HALL12") (pin "2") (pinfunction "2_2") (pintype "passive"))
      (node (ref "HALL13") (pin "2") (pinfunction "2_2") (pintype "passive"))
      (node (ref "HALL14") (pin "2") (pinfunction "2_2") (pintype "passive"))
      (node (ref "HALL15") (pin "2") (pinfunction "2_2") (pintype "passive"))
      (node (ref "HALL2") (pin "2") (pinfunction "2_2") (pintype "passive"))
      (node (ref "HALL3") (pin "2") (pinfunction "2_2") (pintype "passive"))
      (node (ref "HALL4") (pin "2") (pinfunction "2_2") (pintype "passive"))
      (node (ref "HALL5") (pin "2") (pinfunction "2_2") (pintype "passive"))
      (node (ref "HALL6") (pin "2") (pinfunction "2_2") (pintype "passive"))
      (node (ref "HALL7") (pin "2") (pinfunction "2_2") (pintype "passive"))
      (node (ref "HALL8") (pin "2") (pinfunction "2_2") (pintype "passive"))
      (node (ref "HALL9") (pin "2") (pinfunction "2_2") (pintype "passive"))
      (node (ref "U$11") (pin "1") (pinfunction "P$1_1") (pintype "bidirectional"))
      (node (ref "U1") (pin "21") (pinfunction "AGND_21") (pintype "bidirectional"))
    )
    (net (code "3") (name "/ANALOG_0") (class "Default")
      (node (ref "R15") (pin "1") (pinfunction "1_1") (pintype "passive"))
      (node (ref "U$10") (pin "1") (pinfunction "P$1_1") (pintype "bidirectional"))
      (node (ref "U$2") (pin "1") (pinfunction "COM_1") (pintype "output"))
      (node (ref "U1") (pin "22") (pinfunction "ADC7_22") (pintype "bidirectional"))
    )
    (net (code "4") (name "/AREF") (class "Default")
      (node (ref "U$17") (pin "1") (pinfunction "P$1_1") (pintype "bidirectional"))
      (node (ref "U1") (pin "20") (pinfunction "AREF_20") (pintype "bidirectional"))
    )
    (net (code "5") (name "/AVCC") (class "Default")
      (node (ref "C23") (pin "1") (pinfunction "1_1") (pintype "passive"))
      (node (ref "INDUCTOR") (pin "P$1") (pinfunction "1_P$1") (pintype "passive"))
      (node (ref "U1") (pin "18") (pinfunction "AVCC_18") (pintype "bidirectional"))
    )
    (net (code "6") (name "/BATT_MONITOR") (class "Default")
      (node (ref "R29") (pin "2") (pinfunction "2_2") (pintype "passive"))
      (node (ref "R30") (pin "1") (pinfunction "1_1") (pintype "passive"))
      (node (ref "U1") (pin "19") (pinfunction "ADC6_19") (pintype "bidirectional"))
    )
    (net (code "7") (name "/BATT_MONITOR_EN") (class "Default")
      (node (ref "R31") (pin "1") (pinfunction "1_1") (pintype "passive"))
      (node (ref "R32") (pin "2") (pinfunction "2_2") (pintype "passive"))
      (node (ref "U1") (pin "23") (pinfunction "PC0(ADC0)_23") (pintype "bidirectional"))
    )
    (net (code "8") (name "/BUTTON1") (class "Default")
      (node (ref "1") (pin "P$1") (pinfunction "P1_P$1") (pintype "passive"))
      (node (ref "U$6") (pin "1") (pinfunction "P$1_1") (pintype "bidirectional"))
      (node (ref "U1") (pin "32") (pinfunction "PD2(INT0)_32") (pintype "bidirectional"))
    )
    (net (code "9") (name "/BUTTON2") (class "Default")
      (node (ref "2") (pin "P$1") (pinfunction "P1_P$1") (pintype "passive"))
      (node (ref "U$8") (pin "1") (pinfunction "P$1_1") (pintype "bidirectional"))
      (node (ref "U1") (pin "1") (pinfunction "PD3(INT1)_1") (pintype "bidirectional"))
    )
    (net (code "10") (name "/CS_SD") (class "Default")
      (node (ref "U$1") (pin "CS2") (pinfunction "CS_CS2") (pintype "input"))
      (node (ref "U1") (pin "14") (pinfunction "PB2(SS/OC1B)_14") (pintype "bidirectional"))
    )
    (net (code "11") (name "/CS_SHIFT_REG") (class "Default")
      (node (ref "R3") (pin "2") (pinfunction "2_2") (pintype "passive"))
      (node (ref "SHIFT_0") (pin "12") (pinfunction "RCLK_12") (pintype "input"))
      (node (ref "SHIFT_1") (pin "12") (pinfunction "RCLK_12") (pintype "input"))
      (node (ref "U1") (pin "25") (pinfunction "PC2(ADC2)_25") (pintype "bidirectional"))
    )
    (net (code "12") (name "/DTR") (class "Default")
      (node (ref "C5") (pin "1") (pinfunction "1_1") (pintype "passive"))
      (node (ref "JP1") (pin "6") (pinfunction "6_6") (pintype "passive"))
    )
    (net (code "13") (name "/GATE") (class "Default")
      (node (ref "BJT") (pin "3") (pinfunction "C_3") (pintype "passive"))
      (node (ref "P-FET") (pin "1") (pinfunction "G_1") (pintype "passive"))
      (node (ref "R33") (pin "1") (pinfunction "1_1") (pintype "passive"))
    )
    (net (code "14") (name "/HALL0_GND") (class "Default")
      (node (ref "A139_HALL0") (pin "P$3_4") (pinfunction "P$3_P$3_4") (pintype "bidirectional"))
      (node (ref "C50") (pin "2") (pinfunction "2_2") (pintype "passive"))
      (node (ref "HALL0_HEADER") (pin "P$1") (pinfunction "1_P$1") (pintype "passive"))
    )
    (net (code "15") (name "/HALL0_OUTPUT") (class "Default")
      (node (ref "HALL0") (pin "4") (pinfunction "4_4") (pintype "passive"))
      (node (ref "U$2") (pin "9") (pinfunction "X0_9") (pintype "input"))
    )
    (net (code "16") (name "/HALL0_VCC") (class "Default")
      (node (ref "A139_HALL0") (pin "P$1") (pinfunction "P$1_P$1") (pintype "bidirectional"))
      (node (ref "A139_HALL0") (pin "P$6") (pinfunction "P$6_P$6") (pintype "bidirectional"))
      (node (ref "C50") (pin "1") (pinfunction "1_1") (pintype "passive"))
      (node (ref "HALL0_HEADER") (pin "P$2") (pinfunction "2_P$2") (pintype "passive"))
    )
    (net (code "17") (name "/HALL0_VOUT") (class "Default")
      (node (ref "A139_HALL0") (pin "P$2") (pinfunction "P$2_P$2") (pintype "bidirectional"))
      (node (ref "HALL0_HEADER") (pin "P$3") (pinfunction "3_P$3") (pintype "passive"))
    )
    (net (code "18") (name "/HALL0_~{SLEEP_IN}") (class "Default")
      (node (ref "HALL0_HEADER") (pin "P$4") (pinfunction "4_P$4") (pintype "passive"))
      (node (ref "R50") (pin "1") (pinfunction "1_1") (pintype "passive"))
    )
    (net (code "19") (name "/HALL0_~{SLEEP}") (class "Default")
      (node (ref "HALL0") (pin "3") (pinfunction "3_3") (pintype "passive"))
      (node (ref "SHIFT_0") (pin "15") (pinfunction "QA_15") (pintype "tri_state"))
    )
    (net (code "20") (name "/HALL1_GND") (class "Default")
      (node (ref "A139_HALL1") (pin "P$3_4") (pinfunction "P$3_P$3_4") (pintype "bidirectional"))
      (node (ref "C51") (pin "2") (pinfunction "2_2") (pintype "passive"))
      (node (ref "HALL1_HEADER") (pin "P$1") (pinfunction "1_P$1") (pintype "passive"))
    )
    (net (code "21") (name "/HALL1_OUTPUT") (class "Default")
      (node (ref "HALL1") (pin "4") (pinfunction "4_4") (pintype "passive"))
      (node (ref "U$2") (pin "8") (pinfunction "X1_8") (pintype "input"))
    )
    (net (code "22") (name "/HALL1_VCC") (class "Default")
      (node (ref "A139_HALL1") (pin "P$1") (pinfunction "P$1_P$1") (pintype "bidirectional"))
      (node (ref "A139_HALL1") (pin "P$6") (pinfunction "P$6_P$6") (pintype "bidirectional"))
      (node (ref "C51") (pin "1") (pinfunction "1_1") (pintype "passive"))
      (node (ref "HALL1_HEADER") (pin "P$2") (pinfunction "2_P$2") (pintype "passive"))
    )
    (net (code "23") (name "/HALL1_VOUT") (class "Default")
      (node (ref "A139_HALL1") (pin "P$2") (pinfunction "P$2_P$2") (pintype "bidirectional"))
      (node (ref "HALL1_HEADER") (pin "P$3") (pinfunction "3_P$3") (pintype "passive"))
    )
    (net (code "24") (name "/HALL1_~{SLEEP_IN}") (class "Default")
      (node (ref "HALL1_HEADER") (pin "P$4") (pinfunction "4_P$4") (pintype "passive"))
      (node (ref "R51") (pin "1") (pinfunction "1_1") (pintype "passive"))
    )
    (net (code "25") (name "/HALL1_~{SLEEP}") (class "Default")
      (node (ref "HALL1") (pin "3") (pinfunction "3_3") (pintype "passive"))
      (node (ref "SHIFT_0") (pin "1") (pinfunction "QB_1") (pintype "tri_state"))
    )
    (net (code "26") (name "/HALL2_GND") (class "Default")
      (node (ref "A139_HALL2") (pin "P$3_4") (pinfunction "P$3_P$3_4") (pintype "bidirectional"))
      (node (ref "C52") (pin "2") (pinfunction "2_2") (pintype "passive"))
      (node (ref "HALL2_HEADER") (pin "P$1") (pinfunction "1_P$1") (pintype "passive"))
    )
    (net (code "27") (name "/HALL2_OUTPUT") (class "Default")
      (node (ref "HALL2") (pin "4") (pinfunction "4_4") (pintype "passive"))
      (node (ref "U$2") (pin "7") (pinfunction "X2_7") (pintype "input"))
    )
    (net (code "28") (name "/HALL2_VCC") (class "Default")
      (node (ref "A139_HALL2") (pin "P$1") (pinfunction "P$1_P$1") (pintype "bidirectional"))
      (node (ref "A139_HALL2") (pin "P$6") (pinfunction "P$6_P$6") (pintype "bidirectional"))
      (node (ref "C52") (pin "1") (pinfunction "1_1") (pintype "passive"))
      (node (ref "HALL2_HEADER") (pin "P$2") (pinfunction "2_P$2") (pintype "passive"))
    )
    (net (code "29") (name "/HALL2_VOUT") (class "Default")
      (node (ref "A139_HALL2") (pin "P$2") (pinfunction "P$2_P$2") (pintype "bidirectional"))
      (node (ref "HALL2_HEADER") (pin "P$3") (pinfunction "3_P$3") (pintype "passive"))
    )
    (net (code "30") (name "/HALL2_~{SLEEP_IN}") (class "Default")
      (node (ref "HALL2_HEADER") (pin "P$4") (pinfunction "4_P$4") (pintype "passive"))
      (node (ref "R52") (pin "1") (pinfunction "1_1") (pintype "passive"))
    )
    (net (code "31") (name "/HALL2_~{SLEEP}") (class "Default")
      (node (ref "HALL2") (pin "3") (pinfunction "3_3") (pintype "passive"))
      (node (ref "SHIFT_0") (pin "2") (pinfunction "QC_2") (pintype "tri_state"))
    )
    (net (code "32") (name "/HALL3_GND") (class "Default")
      (node (ref "A139_HALL3") (pin "P$3_4") (pinfunction "P$3_P$3_4") (pintype "bidirectional"))
      (node (ref "C53") (pin "2") (pinfunction "2_2") (pintype "passive"))
      (node (ref "HALL3_HEADER") (pin "P$1") (pinfunction "1_P$1") (pintype "passive"))
    )
    (net (code "33") (name "/HALL3_OUTPUT") (class "Default")
      (node (ref "HALL3") (pin "4") (pinfunction "4_4") (pintype "passive"))
      (node (ref "U$2") (pin "6") (pinfunction "X3_6") (pintype "input"))
    )
    (net (code "34") (name "/HALL3_VCC") (class "Default")
      (node (ref "A139_HALL3") (pin "P$1") (pinfunction "P$1_P$1") (pintype "bidirectional"))
      (node (ref "A139_HALL3") (pin "P$6") (pinfunction "P$6_P$6") (pintype "bidirectional"))
      (node (ref "C53") (pin "1") (pinfunction "1_1") (pintype "passive"))
      (node (ref "HALL3_HEADER") (pin "P$2") (pinfunction "2_P$2") (pintype "passive"))
    )
    (net (code "35") (name "/HALL3_VOUT") (class "Default")
      (node (ref "A139_HALL3") (pin "P$2") (pinfunction "P$2_P$2") (pintype "bidirectional"))
      (node (ref "HALL3_HEADER") (pin "P$3") (pinfunction "3_P$3") (pintype "passive"))
    )
    (net (code "36") (name "/HALL3_~{SLEEP_IN}") (class "Default")
      (node (ref "HALL3_HEADER") (pin "P$4") (pinfunction "4_P$4") (pintype "passive"))
      (node (ref "R53") (pin "1") (pinfunction "1_1") (pintype "passive"))
    )
    (net (code "37") (name "/HALL3_~{SLEEP}") (class "Default")
      (node (ref "HALL3") (pin "3") (pinfunction "3_3") (pintype "passive"))
      (node (ref "SHIFT_0") (pin "3") (pinfunction "QD_3") (pintype "tri_state"))
    )
    (net (code "38") (name "/HALL4_GND") (class "Default")
      (node (ref "A139_HALL4") (pin "P$3_4") (pinfunction "P$3_P$3_4") (pintype "bidirectional"))
      (node (ref "C54") (pin "2") (pinfunction "2_2") (pintype "passive"))
      (node (ref "HALL4_HEADER") (pin "P$1") (pinfunction "1_P$1") (pintype "passive"))
    )
    (net (code "39") (name "/HALL4_OUTPUT") (class "Default")
      (node (ref "HALL4") (pin "4") (pinfunction "4_4") (pintype "passive"))
      (node (ref "U$2") (pin "5") (pinfunction "X4_5") (pintype "input"))
    )
    (net (code "40") (name "/HALL4_VCC") (class "Default")
      (node (ref "A139_HALL4") (pin "P$1") (pinfunction "P$1_P$1") (pintype "bidirectional"))
      (node (ref "A139_HALL4") (pin "P$6") (pinfunction "P$6_P$6") (pintype "bidirectional"))
      (node (ref "C54") (pin "1") (pinfunction "1_1") (pintype "passive"))
      (node (ref "HALL4_HEADER") (pin "P$2") (pinfunction "2_P$2") (pintype "passive"))
    )
    (net (code "41") (name "/HALL4_VOUT") (class "Default")
      (node (ref "A139_HALL4") (pin "P$2") (pinfunction "P$2_P$2") (pintype "bidirectional"))
      (node (ref "HALL4_HEADER") (pin "P$3") (pinfunction "3_P$3") (pintype "passive"))
    )
    (net (code "42") (name "/HALL4_~{SLEEP_IN}") (class "Default")
      (node (ref "HALL4_HEADER") (pin "P$4") (pinfunction "4_P$4") (pintype "passive"))
      (node (ref "R54") (pin "1") (pinfunction "1_1") (pintype "passive"))
    )
    (net (code "43") (name "/HALL4_~{SLEEP}") (class "Default")
      (node (ref "HALL4") (pin "3") (pinfunction "3_3") (pintype "passive"))
      (node (ref "SHIFT_0") (pin "4") (pinfunction "QE_4") (pintype "tri_state"))
    )
    (net (code "44") (name "/HALL5_GND") (class "Default")
      (node (ref "A139_HALL5") (pin "P$3_4") (pinfunction "P$3_P$3_4") (pintype "bidirectional"))
      (node (ref "C55") (pin "2") (pinfunction "2_2") (pintype "passive"))
      (node (ref "HALL5_HEADER") (pin "P$1") (pinfunction "1_P$1") (pintype "passive"))
    )
    (net (code "45") (name "/HALL5_OUTPUT") (class "Default")
      (node (ref "HALL5") (pin "4") (pinfunction "4_4") (pintype "passive"))
      (node (ref "U$2") (pin "4") (pinfunction "X5_4") (pintype "input"))
    )
    (net (code "46") (name "/HALL5_VCC") (class "Default")
      (node (ref "A139_HALL5") (pin "P$1") (pinfunction "P$1_P$1") (pintype "bidirectional"))
      (node (ref "A139_HALL5") (pin "P$6") (pinfunction "P$6_P$6") (pintype "bidirectional"))
      (node (ref "C55") (pin "1") (pinfunction "1_1") (pintype "passive"))
      (node (ref "HALL5_HEADER") (pin "P$2") (pinfunction "2_P$2") (pintype "passive"))
    )
    (net (code "47") (name "/HALL5_VOUT") (class "Default")
      (node (ref "A139_HALL5") (pin "P$2") (pinfunction "P$2_P$2") (pintype "bidirectional"))
      (node (ref "HALL5_HEADER") (pin "P$3") (pinfunction "3_P$3") (pintype "passive"))
    )
    (net (code "48") (name "/HALL5_~{SLEEP_IN}") (class "Default")
      (node (ref "HALL5_HEADER") (pin "P$4") (pinfunction "4_P$4") (pintype "passive"))
      (node (ref "R55") (pin "1") (pinfunction "1_1") (pintype "passive"))
    )
    (net (code "49") (name "/HALL5_~{SLEEP}") (class "Default")
      (node (ref "HALL5") (pin "3") (pinfunction "3_3") (pintype "passive"))
      (node (ref "SHIFT_0") (pin "5") (pinfunction "QF_5") (pintype "tri_state"))
    )
    (net (code "50") (name "/HALL6_GND") (class "Default")
      (node (ref "A139_HALL6") (pin "P$3_4") (pinfunction "P$3_P$3_4") (pintype "bidirectional"))
      (node (ref "C56") (pin "2") (pinfunction "2_2") (pintype "passive"))
      (node (ref "HALL6_HEADER") (pin "P$1") (pinfunction "1_P$1") (pintype "passive"))
    )
    (net (code "51") (name "/HALL6_OUTPUT") (class "Default")
      (node (ref "HALL6") (pin "4") (pinfunction "4_4") (pintype "passive"))
      (node (ref "U$2") (pin "3") (pinfunction "X6_3") (pintype "input"))
    )
    (net (code "52") (name "/HALL6_VCC") (class "Default")
      (node (ref "A139_HALL6") (pin "P$1") (pinfunction "P$1_P$1") (pintype "bidirectional"))
      (node (ref "A139_HALL6") (pin "P$6") (pinfunction "P$6_P$6") (pintype "bidirectional"))
      (node (ref "C56") (pin "1") (pinfunction "1_1") (pintype "passive"))
      (node (ref "HALL6_HEADER") (pin "P$2") (pinfunction "2_P$2") (pintype "passive"))
    )
    (net (code "53") (name "/HALL6_VOUT") (class "Default")
      (node (ref "A139_HALL6") (pin "P$2") (pinfunction "P$2_P$2") (pintype "bidirectional"))
      (node (ref "HALL6_HEADER") (pin "P$3") (pinfunction "3_P$3") (pintype "passive"))
    )
    (net (code "54") (name "/HALL6_~{SLEEP_IN}") (class "Default")
      (node (ref "HALL6_HEADER") (pin "P$4") (pinfunction "4_P$4") (pintype "passive"))
      (node (ref "R56") (pin "1") (pinfunction "1_1") (pintype "passive"))
    )
    (net (code "55") (name "/HALL6_~{SLEEP}") (class "Default")
      (node (ref "HALL6") (pin "3") (pinfunction "3_3") (pintype "passive"))
      (node (ref "SHIFT_0") (pin "6") (pinfunction "QG_6") (pintype "tri_state"))
    )
    (net (code "56") (name "/HALL7_GND") (class "Default")
      (node (ref "A139_HALL7") (pin "P$3_4") (pinfunction "P$3_P$3_4") (pintype "bidirectional"))
      (node (ref "C57") (pin "2") (pinfunction "2_2") (pintype "passive"))
      (node (ref "HALL7_HEADER") (pin "P$1") (pinfunction "1_P$1") (pintype "passive"))
    )
    (net (code "57") (name "/HALL7_OUTPUT") (class "Default")
      (node (ref "HALL7") (pin "4") (pinfunction "4_4") (pintype "passive"))
      (node (ref "U$2") (pin "2") (pinfunction "X7_2") (pintype "input"))
    )
    (net (code "58") (name "/HALL7_VCC") (class "Default")
      (node (ref "A139_HALL7") (pin "P$1") (pinfunction "P$1_P$1") (pintype "bidirectional"))
      (node (ref "A139_HALL7") (pin "P$6") (pinfunction "P$6_P$6") (pintype "bidirectional"))
      (node (ref "C57") (pin "1") (pinfunction "1_1") (pintype "passive"))
      (node (ref "HALL7_HEADER") (pin "P$2") (pinfunction "2_P$2") (pintype "passive"))
    )
    (net (code "59") (name "/HALL7_VOUT") (class "Default")
      (node (ref "A139_HALL7") (pin "P$2") (pinfunction "P$2_P$2") (pintype "bidirectional"))
      (node (ref "HALL7_HEADER") (pin "P$3") (pinfunction "3_P$3") (pintype "passive"))
    )
    (net (code "60") (name "/HALL7_~{SLEEP_IN}") (class "Default")
      (node (ref "HALL7_HEADER") (pin "P$4") (pinfunction "4_P$4") (pintype "passive"))
      (node (ref "R57") (pin "1") (pinfunction "1_1") (pintype "passive"))
    )
    (net (code "61") (name "/HALL7_~{SLEEP}") (class "Default")
      (node (ref "HALL7") (pin "3") (pinfunction "3_3") (pintype "passive"))
      (node (ref "SHIFT_0") (pin "7") (pinfunction "QH_7") (pintype "tri_state"))
    )
    (net (code "62") (name "/HALL8_GND") (class "Default")
      (node (ref "A139_HALL8") (pin "P$3_4") (pinfunction "P$3_P$3_4") (pintype "bidirectional"))
      (node (ref "C58") (pin "2") (pinfunction "2_2") (pintype "passive"))
      (node (ref "HALL8_HEADER") (pin "P$1") (pinfunction "1_P$1") (pintype "passive"))
    )
    (net (code "63") (name "/HALL8_OUTPUT") (class "Default")
      (node (ref "HALL8") (pin "4") (pinfunction "4_4") (pintype "passive"))
      (node (ref "U$2") (pin "23") (pinfunction "X8_23") (pintype "input"))
    )
    (net (code "64") (name "/HALL8_VCC") (class "Default")
      (node (ref "A139_HALL8") (pin "P$1") (pinfunction "P$1_P$1") (pintype "bidirectional"))
      (node (ref "A139_HALL8") (pin "P$6") (pinfunction "P$6_P$6") (pintype "bidirectional"))
      (node (ref "C58") (pin "1") (pinfunction "1_1") (pintype "passive"))
      (node (ref "HALL8_HEADER") (pin "P$2") (pinfunction "2_P$2") (pintype "passive"))
    )
    (net (code "65") (name "/HALL8_VOUT") (class "Default")
      (node (ref "A139_HALL8") (pin "P$2") (pinfunction "P$2_P$2") (pintype "bidirectional"))
      (node (ref "HALL8_HEADER") (pin "P$3") (pinfunction "3_P$3") (pintype "passive"))
    )
    (net (code "66") (name "/HALL8_~{SLEEP_IN}") (class "Default")
      (node (ref "HALL8_HEADER") (pin "P$4") (pinfunction "4_P$4") (pintype "passive"))
      (node (ref "R58") (pin "1") (pinfunction "1_1") (pintype "passive"))
    )
    (net (code "67") (name "/HALL8_~{SLEEP}") (class "Default")
      (node (ref "HALL8") (pin "3") (pinfunction "3_3") (pintype "passive"))
      (node (ref "SHIFT_1") (pin "15") (pinfunction "QA_15") (pintype "tri_state"))
    )
    (net (code "68") (name "/HALL9_GND") (class "Default")
      (node (ref "A139_HALL9") (pin "P$3_4") (pinfunction "P$3_P$3_4") (pintype "bidirectional"))
      (node (ref "C59") (pin "2") (pinfunction "2_2") (pintype "passive"))
      (node (ref "HALL9_HEADER") (pin "P$1") (pinfunction "1_P$1") (pintype "passive"))
    )
    (net (code "69") (name "/HALL9_OUTPUT") (class "Default")
      (node (ref "HALL9") (pin "4") (pinfunction "4_4") (pintype "passive"))
      (node (ref "U$2") (pin "22") (pinfunction "X9_22") (pintype "input"))
    )
    (net (code "70") (name "/HALL9_VCC") (class "Default")
      (node (ref "A139_HALL9") (pin "P$1") (pinfunction "P$1_P$1") (pintype "bidirectional"))
      (node (ref "A139_HALL9") (pin "P$6") (pinfunction "P$6_P$6") (pintype "bidirectional"))
      (node (ref "C59") (pin "1") (pinfunction "1_1") (pintype "passive"))
      (node (ref "HALL9_HEADER") (pin "P$2") (pinfunction "2_P$2") (pintype "passive"))
    )
    (net (code "71") (name "/HALL9_VOUT") (class "Default")
      (node (ref "A139_HALL9") (pin "P$2") (pinfunction "P$2_P$2") (pintype "bidirectional"))
      (node (ref "HALL9_HEADER") (pin "P$3") (pinfunction "3_P$3") (pintype "passive"))
    )
    (net (code "72") (name "/HALL9_~{SLEEP_IN}") (class "Default")
      (node (ref "HALL9_HEADER") (pin "P$4") (pinfunction "4_P$4") (pintype "passive"))
      (node (ref "R59") (pin "1") (pinfunction "1_1") (pintype "passive"))
    )
    (net (code "73") (name "/HALL9_~{SLEEP}") (class "Default")
      (node (ref "HALL9") (pin "3") (pinfunction "3_3") (pintype "passive"))
      (node (ref "SHIFT_1") (pin "1") (pinfunction "QB_1") (pintype "tri_state"))
    )
    (net (code "74") (name "/HALL10_GND") (class "Default")
      (node (ref "A139_HALL10") (pin "P$3_4") (pinfunction "P$3_P$3_4") (pintype "bidirectional"))
      (node (ref "C60") (pin "2") (pinfunction "2_2") (pintype "passive"))
      (node (ref "HALL10_HEADER") (pin "P$1") (pinfunction "1_P$1") (pintype "passive"))
    )
    (net (code "75") (name "/HALL10_OUTPUT") (class "Default")
      (node (ref "HALL10") (pin "4") (pinfunction "4_4") (pintype "passive"))
      (node (ref "U$2") (pin "21") (pinfunction "X10_21") (pintype "input"))
    )
    (net (code "76") (name "/HALL10_VCC") (class "Default")
      (node (ref "A139_HALL10") (pin "P$1") (pinfunction "P$1_P$1") (pintype "bidirectional"))
      (node (ref "A139_HALL10") (pin "P$6") (pinfunction "P$6_P$6") (pintype "bidirectional"))
      (node (ref "C60") (pin "1") (pinfunction "1_1") (pintype "passive"))
      (node (ref "HALL10_HEADER") (pin "P$2") (pinfunction "2_P$2") (pintype "passive"))
    )
    (net (code "77") (name "/HALL10_VOUT") (class "Default")
      (node (ref "A139_HALL10") (pin "P$2") (pinfunction "P$2_P$2") (pintype "bidirectional"))
      (node (ref "HALL10_HEADER") (pin "P$3") (pinfunction "3_P$3") (pintype "passive"))
    )
    (net (code "78") (name "/HALL10_~{SLEEP_IN}") (class "Default")
      (node (ref "HALL10_HEADER") (pin "P$4") (pinfunction "4_P$4") (pintype "passive"))
      (node (ref "R60") (pin "1") (pinfunction "1_1") (pintype "passive"))
    )
    (net (code "79") (name "/HALL10_~{SLEEP}") (class "Default")
      (node (ref "HALL10") (pin "3") (pinfunction "3_3") (pintype "passive"))
      (node (ref "SHIFT_1") (pin "2") (pinfunction "QC_2") (pintype "tri_state"))
    )
    (net (code "80") (name "/HALL11_GND") (class "Default")
      (node (ref "A139_HALL11") (pin "P$3_4") (pinfunction "P$3_P$3_4") (pintype "bidirectional"))
      (node (ref "C61") (pin "2") (pinfunction "2_2") (pintype "passive"))
      (node (ref "HALL11_HEADER") (pin "P$1") (pinfunction "1_P$1") (pintype "passive"))
    )
    (net (code "81") (name "/HALL11_OUTPUT") (class "Default")
      (node (ref "HALL11") (pin "4") (pinfunction "4_4") (pintype "passive"))
      (node (ref "U$2") (pin "20") (pinfunction "X11_20") (pintype "input"))
    )
    (net (code "82") (name "/HALL11_VCC") (class "Default")
      (node (ref "A139_HALL11") (pin "P$1") (pinfunction "P$1_P$1") (pintype "bidirectional"))
      (node (ref "A139_HALL11") (pin "P$6") (pinfunction "P$6_P$6") (pintype "bidirectional"))
      (node (ref "C61") (pin "1") (pinfunction "1_1") (pintype "passive"))
      (node (ref "HALL11_HEADER") (pin "P$2") (pinfunction "2_P$2") (pintype "passive"))
    )
    (net (code "83") (name "/HALL11_VOUT") (class "Default")
      (node (ref "A139_HALL11") (pin "P$2") (pinfunction "P$2_P$2") (pintype "bidirectional"))
      (node (ref "HALL11_HEADER") (pin "P$3") (pinfunction "3_P$3") (pintype "passive"))
    )
    (net (code "84") (name "/HALL11_~{SLEEP_IN}") (class "Default")
      (node (ref "HALL11_HEADER") (pin "P$4") (pinfunction "4_P$4") (pintype "passive"))
      (node (ref "R61") (pin "1") (pinfunction "1_1") (pintype "passive"))
    )
    (net (code "85") (name "/HALL11_~{SLEEP}") (class "Default")
      (node (ref "HALL11") (pin "3") (pinfunction "3_3") (pintype "passive"))
      (node (ref "SHIFT_1") (pin "3") (pinfunction "QD_3") (pintype "tri_state"))
    )
    (net (code "86") (name "/HALL12_GND") (class "Default")
      (node (ref "A139_HALL12") (pin "P$3_4") (pinfunction "P$3_P$3_4") (pintype "bidirectional"))
      (node (ref "C62") (pin "2") (pinfunction "2_2") (pintype "passive"))
      (node (ref "HALL12_HEADER") (pin "P$1") (pinfunction "1_P$1") (pintype "passive"))
    )
    (net (code "87") (name "/HALL12_OUTPUT") (class "Default")
      (node (ref "HALL12") (pin "4") (pinfunction "4_4") (pintype "passive"))
      (node (ref "U$2") (pin "19") (pinfunction "X12_19") (pintype "input"))
    )
    (net (code "88") (name "/HALL12_VCC") (class "Default")
      (node (ref "A139_HALL12") (pin "P$1") (pinfunction "P$1_P$1") (pintype "bidirectional"))
      (node (ref "A139_HALL12") (pin "P$6") (pinfunction "P$6_P$6") (pintype "bidirectional"))
      (node (ref "C62") (pin "1") (pinfunction "1_1") (pintype "passive"))
      (node (ref "HALL12_HEADER") (pin "P$2") (pinfunction "2_P$2") (pintype "passive"))
    )
    (net (code "89") (name "/HALL12_VOUT") (class "Default")
      (node (ref "A139_HALL12") (pin "P$2") (pinfunction "P$2_P$2") (pintype "bidirectional"))
      (node (ref "HALL12_HEADER") (pin "P$3") (pinfunction "3_P$3") (pintype "passive"))
    )
    (net (code "90") (name "/HALL12_~{SLEEP_IN}") (class "Default")
      (node (ref "HALL12_HEADER") (pin "P$4") (pinfunction "4_P$4") (pintype "passive"))
      (node (ref "R62") (pin "1") (pinfunction "1_1") (pintype "passive"))
    )
    (net (code "91") (name "/HALL12_~{SLEEP}") (class "Default")
      (node (ref "HALL12") (pin "3") (pinfunction "3_3") (pintype "passive"))
      (node (ref "SHIFT_1") (pin "4") (pinfunction "QE_4") (pintype "tri_state"))
    )
    (net (code "92") (name "/HALL13_GND") (class "Default")
      (node (ref "A139_HALL13") (pin "P$3_4") (pinfunction "P$3_P$3_4") (pintype "bidirectional"))
      (node (ref "C63") (pin "2") (pinfunction "2_2") (pintype "passive"))
      (node (ref "HALL13_HEADER") (pin "P$1") (pinfunction "1_P$1") (pintype "passive"))
    )
    (net (code "93") (name "/HALL13_OUTPUT") (class "Default")
      (node (ref "HALL13") (pin "4") (pinfunction "4_4") (pintype "passive"))
      (node (ref "U$2") (pin "18") (pinfunction "X13_18") (pintype "input"))
    )
    (net (code "94") (name "/HALL13_VCC") (class "Default")
      (node (ref "A139_HALL13") (pin "P$1") (pinfunction "P$1_P$1") (pintype "bidirectional"))
      (node (ref "A139_HALL13") (pin "P$6") (pinfunction "P$6_P$6") (pintype "bidirectional"))
      (node (ref "C63") (pin "1") (pinfunction "1_1") (pintype "passive"))
      (node (ref "HALL13_HEADER") (pin "P$2") (pinfunction "2_P$2") (pintype "passive"))
    )
    (net (code "95") (name "/HALL13_VOUT") (class "Default")
      (node (ref "A139_HALL13") (pin "P$2") (pinfunction "P$2_P$2") (pintype "bidirectional"))
      (node (ref "HALL13_HEADER") (pin "P$3") (pinfunction "3_P$3") (pintype "passive"))
    )
    (net (code "96") (name "/HALL13_~{SLEEP_IN}") (class "Default")
      (node (ref "HALL13_HEADER") (pin "P$4") (pinfunction "4_P$4") (pintype "passive"))
      (node (ref "R63") (pin "1") (pinfunction "1_1") (pintype "passive"))
    )
    (net (code "97") (name "/HALL13_~{SLEEP}") (class "Default")
      (node (ref "HALL13") (pin "3") (pinfunction "3_3") (pintype "passive"))
      (node (ref "SHIFT_1") (pin "5") (pinfunction "QF_5") (pintype "tri_state"))
    )
    (net (code "98") (name "/HALL14_GND") (class "Default")
      (node (ref "A139_HALL14") (pin "P$3_4") (pinfunction "P$3_P$3_4") (pintype "bidirectional"))
      (node (ref "C64") (pin "2") (pinfunction "2_2") (pintype "passive"))
      (node (ref "HALL14_HEADER") (pin "P$1") (pinfunction "1_P$1") (pintype "passive"))
    )
    (net (code "99") (name "/HALL14_OUTPUT") (class "Default")
      (node (ref "HALL14") (pin "4") (pinfunction "4_4") (pintype "passive"))
      (node (ref "U$2") (pin "17") (pinfunction "X14_17") (pintype "input"))
    )
    (net (code "100") (name "/HALL14_VCC") (class "Default")
      (node (ref "A139_HALL14") (pin "P$1") (pinfunction "P$1_P$1") (pintype "bidirectional"))
      (node (ref "A139_HALL14") (pin "P$6") (pinfunction "P$6_P$6") (pintype "bidirectional"))
      (node (ref "C64") (pin "1") (pinfunction "1_1") (pintype "passive"))
      (node (ref "HALL14_HEADER") (pin "P$2") (pinfunction "2_P$2") (pintype "passive"))
    )
    (net (code "101") (name "/HALL14_VOUT") (class "Default")
      (node (ref "A139_HALL14") (pin "P$2") (pinfunction "P$2_P$2") (pintype "bidirectional"))
      (node (ref "HALL14_HEADER") (pin "P$3") (pinfunction "3_P$3") (pintype "passive"))
    )
    (net (code "102") (name "/HALL14_~{SLEEP_IN}") (class "Default")
      (node (ref "HALL14_HEADER") (pin "P$4") (pinfunction "4_P$4") (pintype "passive"))
      (node (ref "R64") (pin "1") (pinfunction "1_1") (pintype "passive"))
    )
    (net (code "103") (name "/HALL14_~{SLEEP}") (class "Default")
      (node (ref "HALL14") (pin "3") (pinfunction "3_3") (pintype "passive"))
      (node (ref "SHIFT_1") (pin "6") (pinfunction "QG_6") (pintype "tri_state"))
    )
    (net (code "104") (name "/HALL15_GND") (class "Default")
      (node (ref "A139_HALL15") (pin "P$3_4") (pinfunction "P$3_P$3_4") (pintype "bidirectional"))
      (node (ref "C65") (pin "2") (pinfunction "2_2") (pintype "passive"))
      (node (ref "HALL15_HEADER") (pin "P$1") (pinfunction "1_P$1") (pintype "passive"))
    )
    (net (code "105") (name "/HALL15_OUTPUT") (class "Default")
      (node (ref "HALL15") (pin "4") (pinfunction "4_4") (pintype "passive"))
      (node (ref "U$2") (pin "16") (pinfunction "X15_16") (pintype "input"))
    )
    (net (code "106") (name "/HALL15_VCC") (class "Default")
      (node (ref "A139_HALL15") (pin "P$1") (pinfunction "P$1_P$1") (pintype "bidirectional"))
      (node (ref "A139_HALL15") (pin "P$6") (pinfunction "P$6_P$6") (pintype "bidirectional"))
      (node (ref "C65") (pin "1") (pinfunction "1_1") (pintype "passive"))
      (node (ref "HALL15_HEADER") (pin "P$2") (pinfunction "2_P$2") (pintype "passive"))
    )
    (net (code "107") (name "/HALL15_VOUT") (class "Default")
      (node (ref "A139_HALL15") (pin "P$2") (pinfunction "P$2_P$2") (pintype "bidirectional"))
      (node (ref "HALL15_HEADER") (pin "P$3") (pinfunction "3_P$3") (pintype "passive"))
    )
    (net (code "108") (name "/HALL15_~{SLEEP_IN}") (class "Default")
      (node (ref "HALL15_HEADER") (pin "P$4") (pinfunction "4_P$4") (pintype "passive"))
      (node (ref "R65") (pin "1") (pinfunction "1_1") (pintype "passive"))
    )
    (net (code "109") (name "/HALL15_~{SLEEP}") (class "Default")
      (node (ref "HALL15") (pin "3") (pinfunction "3_3") (pintype "passive"))
      (node (ref "SHIFT_1") (pin "7") (pinfunction "QH_7") (pintype "tri_state"))
    )
    (net (code "110") (name "/HALL16_GND") (class "Default")
      (node (ref "A139_HALL16") (pin "P$3_4") (pinfunction "P$3_P$3_4") (pintype "bidirectional"))
      (node (ref "C66") (pin "2") (pinfunction "2_2") (pintype "passive"))
      (node (ref "HALL16_HEADER") (pin "P$1") (pinfunction "1_P$1") (pintype "passive"))
    )
    (net (code "111") (name "/HALL16_VCC") (class "Default")
      (node (ref "A139_HALL16") (pin "P$1") (pinfunction "P$1_P$1") (pintype "bidirectional"))
      (node (ref "A139_HALL16") (pin "P$6") (pinfunction "P$6_P$6") (pintype "bidirectional"))
      (node (ref "C66") (pin "1") (pinfunction "1_1") (pintype "passive"))
      (node (ref "HALL16_HEADER") (pin "P$2") (pinfunction "2_P$2") (pintype "passive"))
    )
    (net (code "112") (name "/HALL16_VOUT") (class "Default")
      (node (ref "A139_HALL16") (pin "P$2") (pinfunction "P$2_P$2") (pintype "bidirectional"))
      (node (ref "HALL16_HEADER") (pin "P$3") (pinfunction "3_P$3") (pintype "passive"))
    )
    (net (code "113") (name "/HALL16_~{SLEEP_IN}") (class "Default")
      (node (ref "HALL16_HEADER") (pin "P$4") (pinfunction "4_P$4") (pintype "passive"))
      (node (ref "R66") (pin "1") (pinfunction "1_1") (pintype "passive"))
    )
    (net (code "114") (name "/HALL17_GND") (class "Default")
      (node (ref "A139_HALL17") (pin "P$3_4") (pinfunction "P$3_P$3_4") (pintype "bidirectional"))
      (node (ref "C67") (pin "2") (pinfunction "2_2") (pintype "passive"))
      (node (ref "HALL17_HEADER") (pin "P$1") (pinfunction "1_P$1") (pintype "passive"))
    )
    (net (code "115") (name "/HALL17_VCC") (class "Default")
      (node (ref "A139_HALL17") (pin "P$1") (pinfunction "P$1_P$1") (pintype "bidirectional"))
      (node (ref "A139_HALL17") (pin "P$6") (pinfunction "P$6_P$6") (pintype "bidirectional"))
      (node (ref "C67") (pin "1") (pinfunction "1_1") (pintype "passive"))
      (node (ref "HALL17_HEADER") (pin "P$2") (pinfunction "2_P$2") (pintype "passive"))
    )
    (net (code "116") (name "/HALL17_VOUT") (class "Default")
      (node (ref "A139_HALL17") (pin "P$2") (pinfunction "P$2_P$2") (pintype "bidirectional"))
      (node (ref "HALL17_HEADER") (pin "P$3") (pinfunction "3_P$3") (pintype "passive"))
    )
    (net (code "117") (name "/HALL17_~{SLEEP_IN}") (class "Default")
      (node (ref "HALL17_HEADER") (pin "P$4") (pinfunction "4_P$4") (pintype "passive"))
      (node (ref "R67") (pin "1") (pinfunction "1_1") (pintype "passive"))
    )
    (net (code "118") (name "/HALL18_GND") (class "Default")
      (node (ref "A139_HALL18") (pin "P$3_4") (pinfunction "P$3_P$3_4") (pintype "bidirectional"))
      (node (ref "C68") (pin "2") (pinfunction "2_2") (pintype "passive"))
      (node (ref "HALL18_HEADER") (pin "P$1") (pinfunction "1_P$1") (pintype "passive"))
    )
    (net (code "119") (name "/HALL18_VCC") (class "Default")
      (node (ref "A139_HALL18") (pin "P$1") (pinfunction "P$1_P$1") (pintype "bidirectional"))
      (node (ref "A139_HALL18") (pin "P$6") (pinfunction "P$6_P$6") (pintype "bidirectional"))
      (node (ref "C68") (pin "1") (pinfunction "1_1") (pintype "passive"))
      (node (ref "HALL18_HEADER") (pin "P$2") (pinfunction "2_P$2") (pintype "passive"))
    )
    (net (code "120") (name "/HALL18_VOUT") (class "Default")
      (node (ref "A139_HALL18") (pin "P$2") (pinfunction "P$2_P$2") (pintype "bidirectional"))
      (node (ref "HALL18_HEADER") (pin "P$3") (pinfunction "3_P$3") (pintype "passive"))
    )
    (net (code "121") (name "/HALL18_~{SLEEP_IN}") (class "Default")
      (node (ref "HALL18_HEADER") (pin "P$4") (pinfunction "4_P$4") (pintype "passive"))
      (node (ref "R68") (pin "1") (pinfunction "1_1") (pintype "passive"))
    )
    (net (code "122") (name "/HALL19_GND") (class "Default")
      (node (ref "A139_HALL19") (pin "P$3_4") (pinfunction "P$3_P$3_4") (pintype "bidirectional"))
      (node (ref "C69") (pin "2") (pinfunction "2_2") (pintype "passive"))
      (node (ref "HALL19_HEADER") (pin "P$1") (pinfunction "1_P$1") (pintype "passive"))
    )
    (net (code "123") (name "/HALL19_VCC") (class "Default")
      (node (ref "A139_HALL19") (pin "P$1") (pinfunction "P$1_P$1") (pintype "bidirectional"))
      (node (ref "A139_HALL19") (pin "P$6") (pinfunction "P$6_P$6") (pintype "bidirectional"))
      (node (ref "C69") (pin "1") (pinfunction "1_1") (pintype "passive"))
      (node (ref "HALL19_HEADER") (pin "P$2") (pinfunction "2_P$2") (pintype "passive"))
    )
    (net (code "124") (name "/HALL19_VOUT") (class "Default")
      (node (ref "A139_HALL19") (pin "P$2") (pinfunction "P$2_P$2") (pintype "bidirectional"))
      (node (ref "HALL19_HEADER") (pin "P$3") (pinfunction "3_P$3") (pintype "passive"))
    )
    (net (code "125") (name "/HALL19_~{SLEEP_IN}") (class "Default")
      (node (ref "HALL19_HEADER") (pin "P$4") (pinfunction "4_P$4") (pintype "passive"))
      (node (ref "R69") (pin "1") (pinfunction "1_1") (pintype "passive"))
    )
    (net (code "126") (name "/LED_GRN") (class "Default")
      (node (ref "R2") (pin "2") (pinfunction "2_2") (pintype "passive"))
      (node (ref "U1") (pin "26") (pinfunction "PC3(ADC3)_26") (pintype "bidirectional"))
    )
    (net (code "127") (name "/LED_RED") (class "Default")
      (node (ref "R1") (pin "2") (pinfunction "2_2") (pintype "passive"))
      (node (ref "U1") (pin "2") (pinfunction "PD4(XCK/T0)_2") (pintype "bidirectional"))
    )
    (net (code "128") (name "/MISO") (class "Default")
      (node (ref "J1") (pin "1") (pinfunction "1_1") (pintype "passive"))
      (node (ref "U$1") (pin "MISO7") (pinfunction "DATA_OUT_MISO_MISO7") (pintype "output"))
      (node (ref "U1") (pin "16") (pinfunction "PB4(MISO)_16") (pintype "bidirectional"))
    )
    (net (code "129") (name "/MOSI") (class "Default")
      (node (ref "J1") (pin "4") (pinfunction "4_4") (pintype "passive"))
      (node (ref "SHIFT_0") (pin "14") (pinfunction "SER_14") (pintype "input"))
      (node (ref "U$1") (pin "MOSI3") (pinfunction "DATA_IN_MOSI_MOSI3") (pintype "input"))
      (node (ref "U1") (pin "15") (pinfunction "PB3(MOSI/OC2)_15") (pintype "bidirectional"))
    )
    (net (code "130") (name "/MUX_S0") (class "Default")
      (node (ref "U$2") (pin "10") (pinfunction "S0_10") (pintype "input"))
      (node (ref "U1") (pin "13") (pinfunction "PB1(OC1A)_13") (pintype "bidirectional"))
    )
    (net (code "131") (name "/MUX_S1") (class "Default")
      (node (ref "U$2") (pin "11") (pinfunction "S1_11") (pintype "input"))
      (node (ref "U1") (pin "9") (pinfunction "PD5(T1)_9") (pintype "bidirectional"))
    )
    (net (code "132") (name "/MUX_S2") (class "Default")
      (node (ref "U$2") (pin "14") (pinfunction "S2_14") (pintype "input"))
      (node (ref "U1") (pin "10") (pinfunction "PD6(AIN0)_10") (pintype "bidirectional"))
    )
    (net (code "133") (name "/MUX_S3") (class "Default")
      (node (ref "U$2") (pin "13") (pinfunction "S3_13") (pintype "input"))
      (node (ref "U1") (pin "11") (pinfunction "PD7(AIN1)_11") (pintype "bidirectional"))
    )
    (net (code "134") (name "/MUX_~{EN}") (class "Default")
      (node (ref "R28") (pin "1") (pinfunction "1_1") (pintype "passive"))
      (node (ref "U$2") (pin "15") (pinfunction "~{E}_15") (pintype "input"))
      (node (ref "U1") (pin "12") (pinfunction "PB0(ICP)_12") (pintype "bidirectional"))
    )
    (net (code "135") (name "/PB7") (class "Default")
      (node (ref "PB7") (pin "1") (pinfunction "P$1_1") (pintype "bidirectional"))
      (node (ref "U1") (pin "8") (pinfunction "PB7(XTAL2/TOSC2)_8") (pintype "bidirectional"))
    )
    (net (code "136") (name "/RESET") (class "Default")
      (node (ref "C5") (pin "2") (pinfunction "2_2") (pintype "passive"))
      (node (ref "J1") (pin "5") (pinfunction "5_5") (pintype "passive"))
      (node (ref "R6") (pin "1") (pinfunction "1_1") (pintype "passive"))
      (node (ref "RESET") (pin "P$4") (pinfunction "S1_P$4") (pintype "passive"))
      (node (ref "U$3") (pin "1") (pinfunction "P$1_1") (pintype "bidirectional"))
      (node (ref "U1") (pin "29") (pinfunction "PC6(/RESET)_29") (pintype "bidirectional"))
    )
    (net (code "137") (name "/SCK") (class "Default")
      (node (ref "J1") (pin "3") (pinfunction "3_3") (pintype "passive"))
      (node (ref "SHIFT_0") (pin "11") (pinfunction "SRCLK_11") (pintype "input"))
      (node (ref "SHIFT_1") (pin "11") (pinfunction "SRCLK_11") (pintype "input"))
      (node (ref "U$1") (pin "SCK5") (pinfunction "SCLK_SCK5") (pintype "input"))
      (node (ref "U1") (pin "17") (pinfunction "PB5(SCK)_17") (pintype "bidirectional"))
    )
    (net (code "138") (name "/SCL") (class "Default")
      (node (ref "DS3231M") (pin "8") (pinfunction "P$8_SCL_8") (pintype "bidirectional"))
      (node (ref "OLED") (pin "3") (pinfunction "3_3") (pintype "passive"))
      (node (ref "R7") (pin "1") (pinfunction "1_1") (pintype "passive"))
      (node (ref "U1") (pin "28") (pinfunction "PC5(ADC5/SCL)_28") (pintype "bidirectional"))
    )
    (net (code "139") (name "/SDA") (class "Default")
      (node (ref "DS3231M") (pin "7") (pinfunction "P$7_SDA_7") (pintype "bidirectional"))
      (node (ref "OLED") (pin "4") (pinfunction "4_4") (pintype "passive"))
      (node (ref "R8") (pin "1") (pinfunction "1_1") (pintype "passive"))
      (node (ref "U1") (pin "27") (pinfunction "PC4(ADC4/SDA)_27") (pintype "bidirectional"))
    )
    (net (code "140") (name "/SHIFT_CLEAR") (class "Default")
      (node (ref "R14") (pin "1") (pinfunction "1_1") (pintype "passive"))
      (node (ref "SHIFT_0") (pin "10") (pinfunction "~{SRCLR}_10") (pintype "input"))
      (node (ref "SHIFT_1") (pin "10") (pinfunction "~{SRCLR}_10") (pintype "input"))
      (node (ref "U1") (pin "24") (pinfunction "PC1(ADC1)_24") (pintype "bidirectional"))
    )
    (net (code "141") (name "/TO_FTDI_RX") (class "Default")
      (node (ref "JP1") (pin "5") (pinfunction "5_5") (pintype "passive"))
      (node (ref "U1") (pin "31") (pinfunction "PD1(TXD)_31") (pintype "bidirectional"))
    )
    (net (code "142") (name "/TO_FTDI_TX") (class "Default")
      (node (ref "JP1") (pin "4") (pinfunction "4_4") (pintype "passive"))
      (node (ref "U1") (pin "30") (pinfunction "PD0(RXD)_30") (pintype "bidirectional"))
    )
    (net (code "143") (name "/VBAT") (class "Default")
      (node (ref "CR1220_BATTERY") (pin "P$1") (pinfunction "VBAT_P$1") (pintype "power_in"))
      (node (ref "CR1220_BATTERY") (pin "P$2") (pinfunction "P$2_P$2") (pintype "power_in"))
      (node (ref "DS3231M") (pin "6") (pinfunction "P$6_VBAT_6") (pintype "bidirectional"))
    )
    (net (code "144") (name "/VBATTERY") (class "Default")
      (node (ref "LTC4411") (pin "1") (pinfunction "VIN_1") (pintype "passive"))
      (node (ref "MOLEX_KK") (pin "2") (pinfunction "S_2") (pintype "passive"))
      (node (ref "PRIMARY_BATTERY") (pin "VBAT") (pinfunction "VBAT_VBAT") (pintype "power_in"))
    )
    (net (code "145") (name "/VRAW1") (class "Default")
      (node (ref "C1") (pin "+") (pinfunction "+_+") (pintype "passive"))
      (node (ref "C25") (pin "1") (pinfunction "1_1") (pintype "passive"))
      (node (ref "LTC4411") (pin "5") (pinfunction "OUT_5") (pintype "passive"))
      (node (ref "MCP1700T-3302") (pin "3") (pinfunction "VIN_3") (pintype "input"))
      (node (ref "P-FET") (pin "2") (pinfunction "S_2") (pintype "passive"))
      (node (ref "R33") (pin "2") (pinfunction "2_2") (pintype "passive"))
      (node (ref "SCHOTTKY") (pin "C") (pinfunction "C_C") (pintype "passive"))
    )
    (net (code "146") (name "/V_JACK") (class "Default")
      (node (ref "2,1MM_JACK") (pin "P$1") (pinfunction "PWR_P$1") (pintype "bidirectional"))
      (node (ref "SCHOTTKY") (pin "A") (pinfunction "A_A") (pintype "passive"))
    )
    (net (code "147") (name "/~{SLEEP0}") (class "Default")
      (node (ref "A139_HALL0") (pin "P$5") (pinfunction "P$5_P$5") (pintype "bidirectional"))
      (node (ref "R50") (pin "2") (pinfunction "2_2") (pintype "passive"))
    )
    (net (code "148") (name "/~{SLEEP1}") (class "Default")
      (node (ref "A139_HALL1") (pin "P$5") (pinfunction "P$5_P$5") (pintype "bidirectional"))
      (node (ref "R51") (pin "2") (pinfunction "2_2") (pintype "passive"))
    )
    (net (code "149") (name "/~{SLEEP2}") (class "Default")
      (node (ref "A139_HALL2") (pin "P$5") (pinfunction "P$5_P$5") (pintype "bidirectional"))
      (node (ref "R52") (pin "2") (pinfunction "2_2") (pintype "passive"))
    )
    (net (code "150") (name "/~{SLEEP3}") (class "Default")
      (node (ref "A139_HALL3") (pin "P$5") (pinfunction "P$5_P$5") (pintype "bidirectional"))
      (node (ref "R53") (pin "2") (pinfunction "2_2") (pintype "passive"))
    )
    (net (code "151") (name "/~{SLEEP4}") (class "Default")
      (node (ref "A139_HALL4") (pin "P$5") (pinfunction "P$5_P$5") (pintype "bidirectional"))
      (node (ref "R54") (pin "2") (pinfunction "2_2") (pintype "passive"))
    )
    (net (code "152") (name "/~{SLEEP5}") (class "Default")
      (node (ref "A139_HALL5") (pin "P$5") (pinfunction "P$5_P$5") (pintype "bidirectional"))
      (node (ref "R55") (pin "2") (pinfunction "2_2") (pintype "passive"))
    )
    (net (code "153") (name "/~{SLEEP6}") (class "Default")
      (node (ref "A139_HALL6") (pin "P$5") (pinfunction "P$5_P$5") (pintype "bidirectional"))
      (node (ref "R56") (pin "2") (pinfunction "2_2") (pintype "passive"))
    )
    (net (code "154") (name "/~{SLEEP7}") (class "Default")
      (node (ref "A139_HALL7") (pin "P$5") (pinfunction "P$5_P$5") (pintype "bidirectional"))
      (node (ref "R57") (pin "2") (pinfunction "2_2") (pintype "passive"))
    )
    (net (code "155") (name "/~{SLEEP8}") (class "Default")
      (node (ref "A139_HALL8") (pin "P$5") (pinfunction "P$5_P$5") (pintype "bidirectional"))
      (node (ref "R58") (pin "2") (pinfunction "2_2") (pintype "passive"))
    )
    (net (code "156") (name "/~{SLEEP9}") (class "Default")
      (node (ref "A139_HALL9") (pin "P$5") (pinfunction "P$5_P$5") (pintype "bidirectional"))
      (node (ref "R59") (pin "2") (pinfunction "2_2") (pintype "passive"))
    )
    (net (code "157") (name "/~{SLEEP10}") (class "Default")
      (node (ref "A139_HALL10") (pin "P$5") (pinfunction "P$5_P$5") (pintype "bidirectional"))
      (node (ref "R60") (pin "2") (pinfunction "2_2") (pintype "passive"))
    )
    (net (code "158") (name "/~{SLEEP11}") (class "Default")
      (node (ref "A139_HALL11") (pin "P$5") (pinfunction "P$5_P$5") (pintype "bidirectional"))
      (node (ref "R61") (pin "2") (pinfunction "2_2") (pintype "passive"))
    )
    (net (code "159") (name "/~{SLEEP12}") (class "Default")
      (node (ref "A139_HALL12") (pin "P$5") (pinfunction "P$5_P$5") (pintype "bidirectional"))
      (node (ref "R62") (pin "2") (pinfunction "2_2") (pintype "passive"))
    )
    (net (code "160") (name "/~{SLEEP13}") (class "Default")
      (node (ref "A139_HALL13") (pin "P$5") (pinfunction "P$5_P$5") (pintype "bidirectional"))
      (node (ref "R63") (pin "2") (pinfunction "2_2") (pintype "passive"))
    )
    (net (code "161") (name "/~{SLEEP14}") (class "Default")
      (node (ref "A139_HALL14") (pin "P$5") (pinfunction "P$5_P$5") (pintype "bidirectional"))
      (node (ref "R64") (pin "2") (pinfunction "2_2") (pintype "passive"))
    )
    (net (code "162") (name "/~{SLEEP15}") (class "Default")
      (node (ref "A139_HALL15") (pin "P$5") (pinfunction "P$5_P$5") (pintype "bidirectional"))
      (node (ref "R65") (pin "2") (pinfunction "2_2") (pintype "passive"))
    )
    (net (code "163") (name "/~{SLEEP16}") (class "Default")
      (node (ref "A139_HALL16") (pin "P$5") (pinfunction "P$5_P$5") (pintype "bidirectional"))
      (node (ref "R66") (pin "2") (pinfunction "2_2") (pintype "passive"))
    )
    (net (code "164") (name "/~{SLEEP17}") (class "Default")
      (node (ref "A139_HALL17") (pin "P$5") (pinfunction "P$5_P$5") (pintype "bidirectional"))
      (node (ref "R67") (pin "2") (pinfunction "2_2") (pintype "passive"))
    )
    (net (code "165") (name "/~{SLEEP18}") (class "Default")
      (node (ref "A139_HALL18") (pin "P$5") (pinfunction "P$5_P$5") (pintype "bidirectional"))
      (node (ref "R68") (pin "2") (pinfunction "2_2") (pintype "passive"))
    )
    (net (code "166") (name "/~{SLEEP19}") (class "Default")
      (node (ref "A139_HALL19") (pin "P$5") (pinfunction "P$5_P$5") (pintype "bidirectional"))
      (node (ref "R69") (pin "2") (pinfunction "2_2") (pintype "passive"))
    )
    (net (code "167") (name "GND") (class "Default")
      (node (ref "1") (pin "S$1") (pinfunction "S1_S$1") (pintype "passive"))
      (node (ref "2") (pin "S$1") (pinfunction "S1_S$1") (pintype "passive"))
      (node (ref "2,1MM_JACK") (pin "P$2") (pinfunction "GND_P$2") (pintype "bidirectional"))
      (node (ref "BJT") (pin "2") (pinfunction "E_2") (pintype "passive"))
      (node (ref "C1") (pin "-") (pinfunction "-_-") (pintype "passive"))
      (node (ref "C10") (pin "2") (pinfunction "2_2") (pintype "passive"))
      (node (ref "C2") (pin "-") (pinfunction "-_-") (pintype "passive"))
      (node (ref "C25") (pin "2") (pinfunction "2_2") (pintype "passive"))
      (node (ref "C3") (pin "2") (pinfunction "2_2") (pintype "passive"))
      (node (ref "C4") (pin "2") (pinfunction "2_2") (pintype "passive"))
      (node (ref "C6") (pin "2") (pinfunction "2_2") (pintype "passive"))
      (node (ref "C7") (pin "2") (pinfunction "2_2") (pintype "passive"))
      (node (ref "C8") (pin "2") (pinfunction "2_2") (pintype "passive"))
      (node (ref "C9") (pin "2") (pinfunction "2_2") (pintype "passive"))
      (node (ref "CR1220_BATTERY") (pin "GND") (pinfunction "GND_GND") (pintype "power_in"))
      (node (ref "DS3231M") (pin "5") (pinfunction "P$5_GND_5") (pintype "power_in"))
      (node (ref "GND") (pin "1") (pinfunction "P$1_1") (pintype "bidirectional"))
      (node (ref "GROUND_CON") (pin "1") (pinfunction "P$1_1") (pintype "bidirectional"))
      (node (ref "J1") (pin "6") (pinfunction "6_6") (pintype "passive"))
      (node (ref "JP1") (pin "1") (pinfunction "1_1") (pintype "passive"))
      (node (ref "JP1") (pin "2") (pinfunction "2_2") (pintype "passive"))
      (node (ref "LED1") (pin "C") (pinfunction "C_C") (pintype "passive"))
      (node (ref "LED2") (pin "C") (pinfunction "C_C") (pintype "passive"))
      (node (ref "LTC4411") (pin "2") (pinfunction "GND_2") (pintype "passive"))
      (node (ref "LTC4411") (pin "3") (pinfunction "CTL_3") (pintype "passive"))
      (node (ref "MCP1700T-3302") (pin "1") (pinfunction "GND_1") (pintype "passive"))
      (node (ref "MOLEX_KK") (pin "1") (pinfunction "S_1") (pintype "passive"))
      (node (ref "OLED") (pin "1") (pinfunction "1_1") (pintype "passive"))
      (node (ref "PRIMARY_BATTERY") (pin "GND") (pinfunction "GND_GND") (pintype "power_in"))
      (node (ref "R29") (pin "1") (pinfunction "1_1") (pintype "passive"))
      (node (ref "R3") (pin "1") (pinfunction "1_1") (pintype "passive"))
      (node (ref "R32") (pin "1") (pinfunction "1_1") (pintype "passive"))
      (node (ref "RESET") (pin "P$2") (pinfunction "P1_P$2") (pintype "passive"))
      (node (ref "SHIFT_0") (pin "13") (pinfunction "~{OE}_13") (pintype "input"))
      (node (ref "SHIFT_0") (pin "8") (pinfunction "GND_8") (pintype "power_in"))
      (node (ref "SHIFT_1") (pin "13") (pinfunction "~{OE}_13") (pintype "input"))
      (node (ref "SHIFT_1") (pin "8") (pinfunction "GND_8") (pintype "power_in"))
      (node (ref "U$1") (pin "GND6") (pinfunction "VSS_GND_GND6") (pintype "power_in"))
      (node (ref "U$1") (pin "MNT1") (pinfunction "GND1_MNT1") (pintype "power_in"))
      (node (ref "U$1") (pin "MNT2") (pinfunction "GND2_MNT2") (pintype "power_in"))
      (node (ref "U$1") (pin "MNT3") (pinfunction "GND3_MNT3") (pintype "power_in"))
      (node (ref "U$1") (pin "MNT4") (pinfunction "GND4_MNT4") (pintype "power_in"))
      (node (ref "U$2") (pin "12") (pinfunction "GND_12") (pintype "power_in"))
      (node (ref "U$4") (pin "1") (pinfunction "P$1_1") (pintype "bidirectional"))
      (node (ref "U$7") (pin "1") (pinfunction "P$1_1") (pintype "bidirectional"))
      (node (ref "U$9") (pin "1") (pinfunction "P$1_1") (pintype "bidirectional"))
      (node (ref "U1") (pin "3") (pinfunction "GND_3") (pintype "bidirectional"))
      (node (ref "U1") (pin "5") (pinfunction "GND_5") (pintype "bidirectional"))
    )
    (net (code "168") (name "Net-(BJT-B)") (class "Default")
      (node (ref "BJT") (pin "1") (pinfunction "B_1") (pintype "passive"))
      (node (ref "R31") (pin "2") (pinfunction "2_2") (pintype "passive"))
    )
    (net (code "169") (name "Net-(LED1-PadA)") (class "Default")
      (node (ref "LED1") (pin "A") (pinfunction "A_A") (pintype "passive"))
      (node (ref "R1") (pin "1") (pinfunction "1_1") (pintype "passive"))
    )
    (net (code "170") (name "Net-(LED2-PadA)") (class "Default")
      (node (ref "LED2") (pin "A") (pinfunction "A_A") (pintype "passive"))
      (node (ref "R2") (pin "1") (pinfunction "1_1") (pintype "passive"))
    )
    (net (code "171") (name "Net-(LTC4411-STAT)") (class "Default")
      (node (ref "LTC4411") (pin "4") (pinfunction "STAT_4") (pintype "passive"))
      (node (ref "R34") (pin "1") (pinfunction "1_1") (pintype "passive"))
    )
    (net (code "172") (name "Net-(P-FET-D)") (class "Default")
      (node (ref "P-FET") (pin "3") (pinfunction "D_3") (pintype "passive"))
      (node (ref "R30") (pin "2") (pinfunction "2_2") (pintype "passive"))
    )
    (net (code "173") (name "Net-(SHIFT_0-QH*)") (class "Default")
      (node (ref "SHIFT_0") (pin "9") (pinfunction "QH*_9") (pintype "tri_state"))
      (node (ref "SHIFT_1") (pin "14") (pinfunction "SER_14") (pintype "input"))
    )
    (net (code "174") (name "Net-(U$1-DAT1_NC)") (class "Default")
      (node (ref "R5") (pin "1") (pinfunction "1_1") (pintype "passive"))
      (node (ref "U$1") (pin "NC1") (pinfunction "DAT1_NC_NC1") (pintype "bidirectional"))
    )
    (net (code "175") (name "Net-(U$1-DAT2_RES)") (class "Default")
      (node (ref "R4") (pin "1") (pinfunction "1_1") (pintype "passive"))
      (node (ref "U$1") (pin "RES8") (pinfunction "DAT2_RES_RES8") (pintype "bidirectional"))
    )
    (net (code "176") (name "VCC") (class "Default")
      (node (ref "C10") (pin "1") (pinfunction "1_1") (pintype "passive"))
      (node (ref "C2") (pin "+") (pinfunction "+_+") (pintype "passive"))
      (node (ref "C3") (pin "1") (pinfunction "1_1") (pintype "passive"))
      (node (ref "C4") (pin "1") (pinfunction "1_1") (pintype "passive"))
      (node (ref "C6") (pin "1") (pinfunction "1_1") (pintype "passive"))
      (node (ref "C7") (pin "1") (pinfunction "1_1") (pintype "passive"))
      (node (ref "C8") (pin "1") (pinfunction "1_1") (pintype "passive"))
      (node (ref "C9") (pin "1") (pinfunction "1_1") (pintype "passive"))
      (node (ref "DS3231M") (pin "2") (pinfunction "P$2_VCC_2") (pintype "power_in"))
      (node (ref "HALL0") (pin "1") (pinfunction "1_1") (pintype "passive"))
      (node (ref "HALL1") (pin "1") (pinfunction "1_1") (pintype "passive"))
      (node (ref "HALL10") (pin "1") (pinfunction "1_1") (pintype "passive"))
      (node (ref "HALL11") (pin "1") (pinfunction "1_1") (pintype "passive"))
      (node (ref "HALL12") (pin "1") (pinfunction "1_1") (pintype "passive"))
      (node (ref "HALL13") (pin "1") (pinfunction "1_1") (pintype "passive"))
      (node (ref "HALL14") (pin "1") (pinfunction "1_1") (pintype "passive"))
      (node (ref "HALL15") (pin "1") (pinfunction "1_1") (pintype "passive"))
      (node (ref "HALL2") (pin "1") (pinfunction "1_1") (pintype "passive"))
      (node (ref "HALL3") (pin "1") (pinfunction "1_1") (pintype "passive"))
      (node (ref "HALL4") (pin "1") (pinfunction "1_1") (pintype "passive"))
      (node (ref "HALL5") (pin "1") (pinfunction "1_1") (pintype "passive"))
      (node (ref "HALL6") (pin "1") (pinfunction "1_1") (pintype "passive"))
      (node (ref "HALL7") (pin "1") (pinfunction "1_1") (pintype "passive"))
      (node (ref "HALL8") (pin "1") (pinfunction "1_1") (pintype "passive"))
      (node (ref "HALL9") (pin "1") (pinfunction "1_1") (pintype "passive"))
      (node (ref "INDUCTOR") (pin "P$2") (pinfunction "2_P$2") (pintype "passive"))
      (node (ref "J1") (pin "2") (pinfunction "2_2") (pintype "passive"))
      (node (ref "JP1") (pin "3") (pinfunction "3_3") (pintype "passive"))
      (node (ref "MCP1700T-3302") (pin "2") (pinfunction "VOUT_2") (pintype "output"))
      (node (ref "OLED") (pin "2") (pinfunction "2_2") (pintype "passive"))
      (node (ref "R14") (pin "2") (pinfunction "2_2") (pintype "passive"))
      (node (ref "R15") (pin "2") (pinfunction "2_2") (pintype "passive"))
      (node (ref "R28") (pin "2") (pinfunction "2_2") (pintype "passive"))
      (node (ref "R34") (pin "2") (pinfunction "2_2") (pintype "passive"))
      (node (ref "R4") (pin "2") (pinfunction "2_2") (pintype "passive"))
      (node (ref "R5") (pin "2") (pinfunction "2_2") (pintype "passive"))
      (node (ref "R6") (pin "2") (pinfunction "2_2") (pintype "passive"))
      (node (ref "R7") (pin "2") (pinfunction "2_2") (pintype "passive"))
      (node (ref "R8") (pin "2") (pinfunction "2_2") (pintype "passive"))
      (node (ref "R9") (pin "2") (pinfunction "2_2") (pintype "passive"))
      (node (ref "SHIFT_0") (pin "16") (pinfunction "VCC_16") (pintype "power_in"))
      (node (ref "SHIFT_1") (pin "16") (pinfunction "VCC_16") (pintype "power_in"))
      (node (ref "U$1") (pin "VDD4") (pinfunction "VDD_VDD4") (pintype "power_in"))
      (node (ref "U$2") (pin "24") (pinfunction "VCC_24") (pintype "power_in"))
      (node (ref "U1") (pin "4") (pinfunction "VCC_4") (pintype "bidirectional"))
      (node (ref "U1") (pin "6") (pinfunction "VCC_6") (pintype "bidirectional"))
    )
    (net (code "177") (name "unconnected-(1-PadP)") (class "Default")
      (node (ref "1") (pin "P") (pinfunction "P_P") (pintype "passive"))
    )
    (net (code "178") (name "unconnected-(1-PadS)") (class "Default")
      (node (ref "1") (pin "S") (pinfunction "S_S") (pintype "passive"))
    )
    (net (code "179") (name "unconnected-(2,1MM_JACK-GNDBREAK-PadP$3)") (class "Default")
      (node (ref "2,1MM_JACK") (pin "P$3") (pinfunction "GNDBREAK_P$3") (pintype "bidirectional"))
    )
    (net (code "180") (name "unconnected-(2-PadP)") (class "Default")
      (node (ref "2") (pin "P") (pinfunction "P_P") (pintype "passive"))
    )
    (net (code "181") (name "unconnected-(2-PadS)") (class "Default")
      (node (ref "2") (pin "S") (pinfunction "S_S") (pintype "passive"))
    )
    (net (code "182") (name "unconnected-(DS3231M-P$3_INT-Pad3)") (class "Default")
      (node (ref "DS3231M") (pin "3") (pinfunction "P$3_INT_3") (pintype "bidirectional"))
    )
    (net (code "183") (name "unconnected-(DS3231M-P$4_RST-Pad4)") (class "Default")
      (node (ref "DS3231M") (pin "4") (pinfunction "P$4_RST_4") (pintype "bidirectional"))
    )
    (net (code "184") (name "unconnected-(RESET-P-PadP$1)") (class "Default")
      (node (ref "RESET") (pin "P$1") (pinfunction "P_P$1") (pintype "passive"))
    )
    (net (code "185") (name "unconnected-(RESET-S-PadP$3)") (class "Default")
      (node (ref "RESET") (pin "P$3") (pinfunction "S_P$3") (pintype "passive"))
    )
    (net (code "186") (name "unconnected-(SHIFT_1-QH*-Pad9)") (class "Default")
      (node (ref "SHIFT_1") (pin "9") (pinfunction "QH*_9") (pintype "tri_state"))
    )
    (net (code "187") (name "unconnected-(U$1-CARD_DETECT-PadCARD_DETECT1)") (class "Default")
      (node (ref "U$1") (pin "CARD_DETECT1") (pinfunction "CARD_DETECT_CARD_DETECT1") (pintype "passive"))
    )
    (net (code "188") (name "unconnected-(U$1-CARD_DETECT1-PadCARD_DETECT2)") (class "Default")
      (node (ref "U$1") (pin "CARD_DETECT2") (pinfunction "CARD_DETECT1_CARD_DETECT2") (pintype "passive"))
    )
  )
)
